# CM5_Adapter.net
KiCad netlist of a schematic drawn in Altium Designer
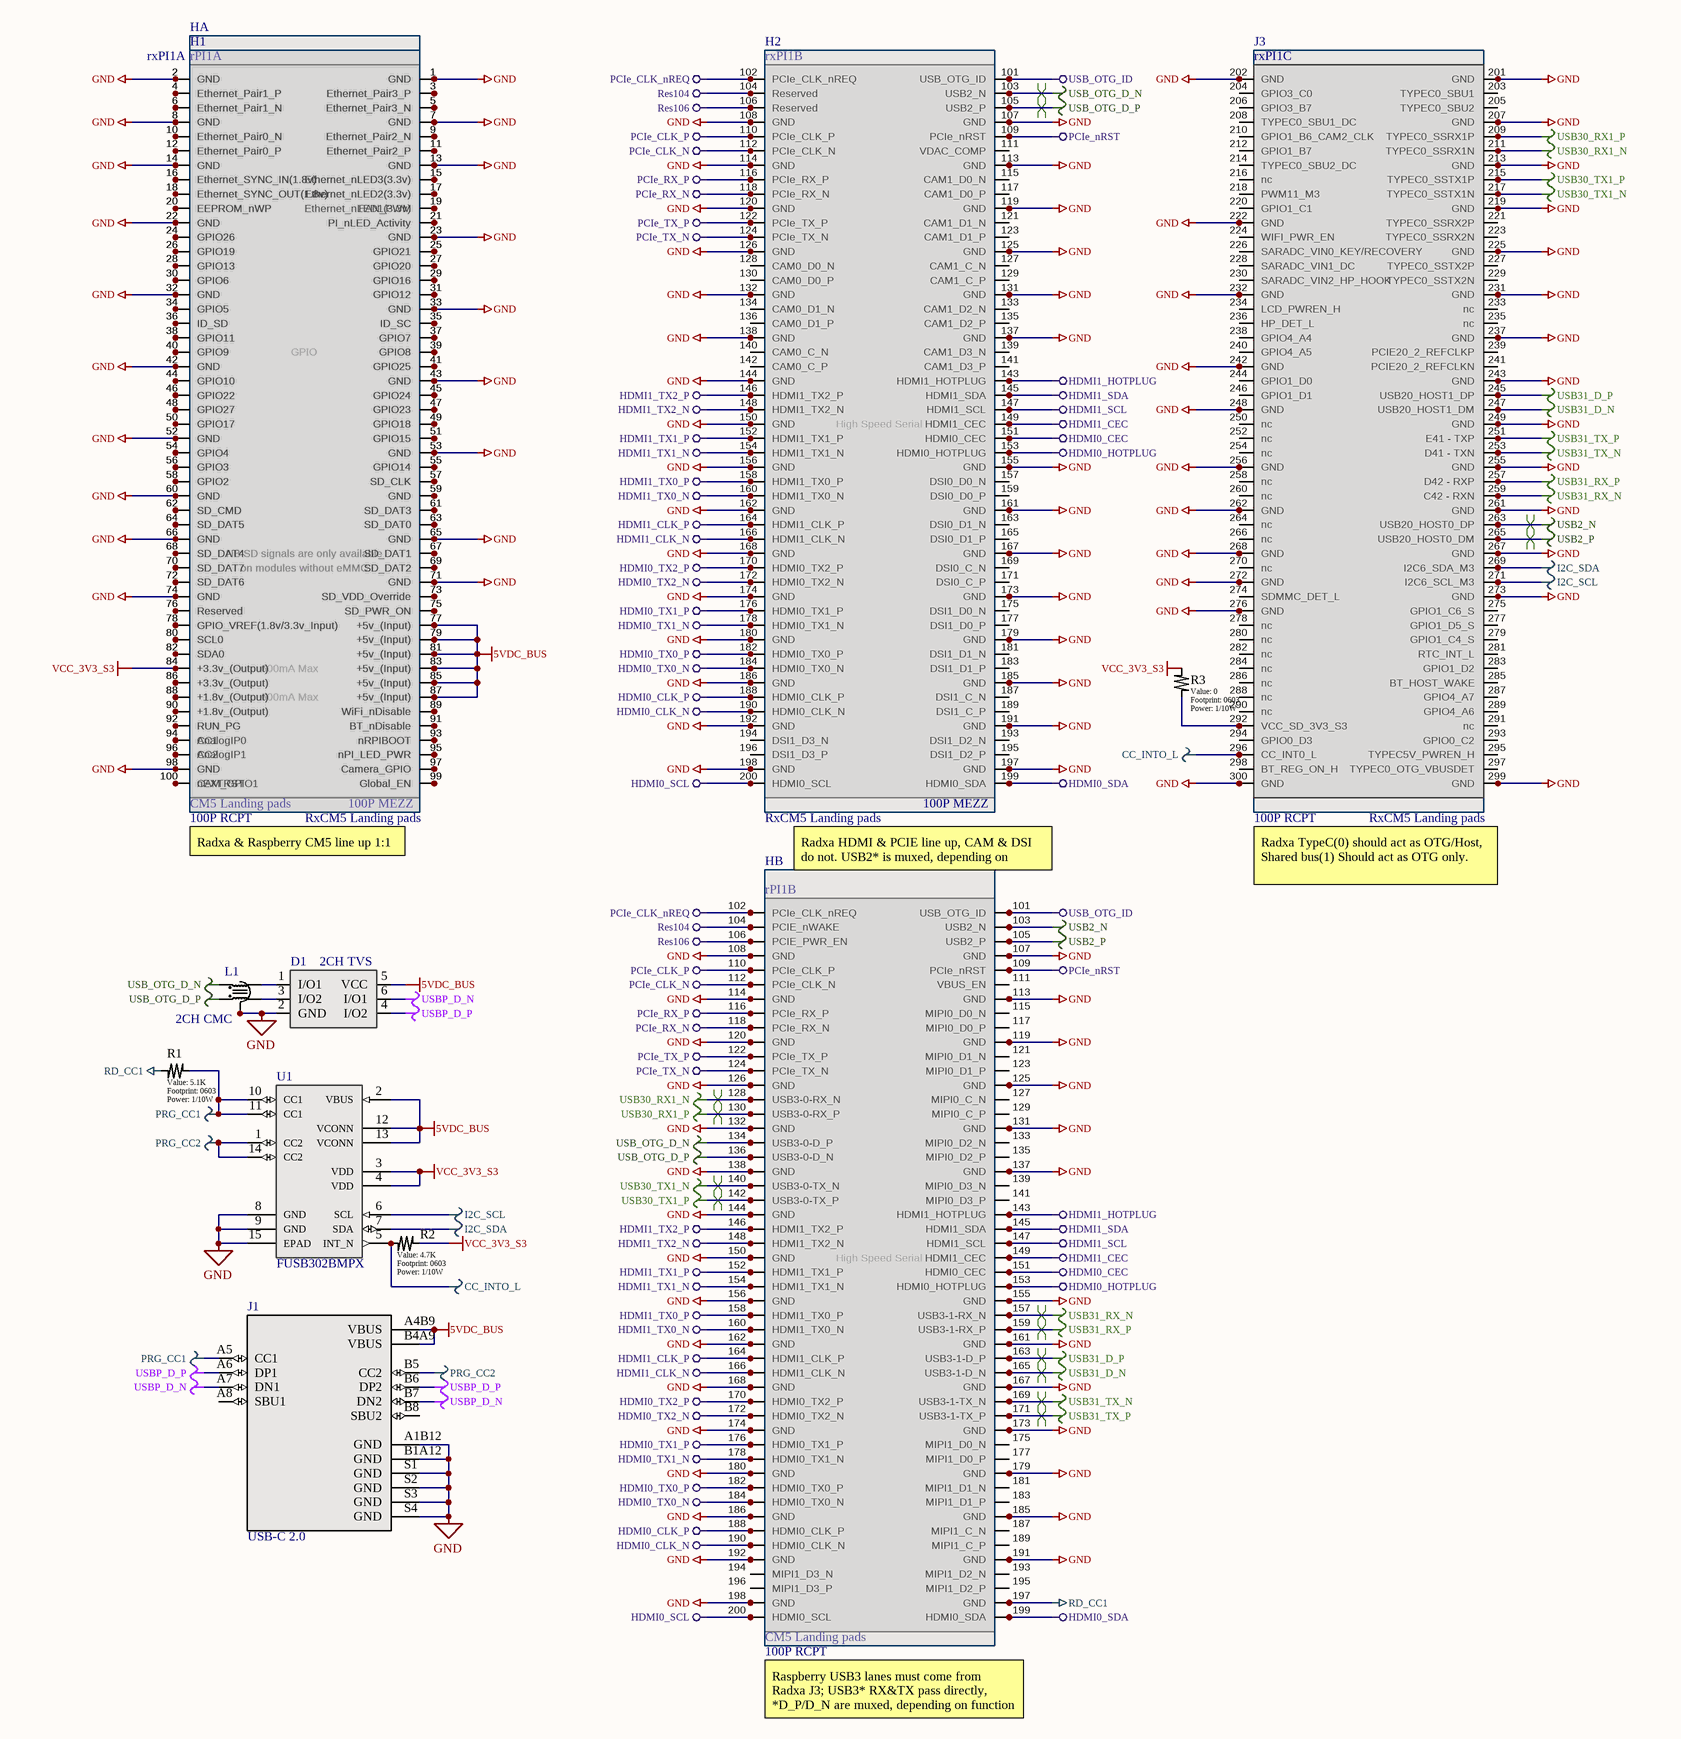
[diagram p0: CM5 Adapter.SchDoc]

(export (version "E")
  (design (tool "Eeschema 10.0.6"))
  (components
    (comp (ref "D1")
      (value "2CH TVS")
      (footprint "FP-SOT886-MFG")
      (description "TVS DIODE 5.5V 6XSON SOT886")
      (fields
        (field (name "OCTOPART") "https://octopart.com/prtr5v0u2f%2C115-nexperia-78741690")
        (field (name "MANUFACTURER") "Nexperia")
      )
      (libsource (lib "Diodes") (part "PRTR5V0U2F,115"))
    )
    (comp (ref "H1")
      (value "100P RCPT")
      (footprint "DF40C-100DS-0.4V(51)")
      (description "100 Position Connector Receptacle, Center Strip Contacts Surface Mount Gold")
      (fields (field (name "MF") "Hirose") (field (name "MP") "DF40C-100DS-0.4V(51)"))
      (libsource (lib "Connectors") (part "DF40-100DS RCPT_1"))
    )
    (comp (ref "H2")
      (value "100P MEZZ")
      (footprint "DF40C-100DS-0.4V(51)")
      (description "100 Position Connector Receptacle, Center Strip Contacts Surface Mount Gold")
      (fields (field (name "MF") "Hirose") (field (name "MP") "DF40C-100DS-0.4V(51)"))
      (libsource (lib "Connectors") (part "DF40-100DS RCPT_1"))
    )
    (comp (ref "HA")
      (value "100P MEZZ")
      (footprint "DF40C-100DP-0.4V(51)")
      (description "100 Position Connector Receptacle, Center Strip Contacts Surface Mount Gold")
      (fields (field (name "MF") "Hirose") (field (name "MP") "DF40C-100DS-0.4V(51)"))
      (libsource (lib "SOC_Carrier") (part "DF40-XX-100DS RCPT"))
    )
    (comp (ref "HB")
      (value "100P RCPT")
      (footprint "DF40C-100DP-0.4V(51)")
      (description "100 Position Connector Receptacle, Center Strip Contacts Surface Mount Gold")
      (fields (field (name "MF") "Hirose") (field (name "MP") "DF40C-100DS-0.4V(51)"))
      (libsource (lib "SOC_Carrier") (part "DF40-XX-100DS RCPT"))
    )
    (comp (ref "J1")
      (value "USB-C 2.0")
      (footprint "GT-USB-7010ASV")
      (libsource (lib "Connectors") (part "12402012E212A"))
    )
    (comp (ref "J3")
      (value "100P RCPT")
      (footprint "DF40C-100DS-0.4V(51)")
      (description "100 Position Connector Receptacle, Center Strip Contacts Surface Mount Gold")
      (fields (field (name "MF") "Hirose") (field (name "MP") "DF40C-100DS-0.4V(51)"))
      (libsource (lib "") (part "DF40-100DS RCPT_1_1"))
    )
    (comp (ref "L1")
      (value "2CH CMC")
      (footprint "SMD-6-2CH")
      (description "35Ω@100MHz -40℃~+85℃ 4Ω 5V 2 100mA SMD Common Mode Filters ROHS")
      (libsource (lib "Inductors") (part "ICMEF112P350MFR"))
    )
    (comp (ref "R1")
      (value "5.1K")
      (footprint "0603")
      (fields
        (field (name "TOLERANCE") "1%")
        (field (name "POWER") "1/10W")
        (field (name "Comment") "Generic Resistor")
      )
      (libsource (lib "Resistors") (part "Generic Resistor"))
    )
    (comp (ref "R2")
      (value "4.7K")
      (footprint "0603")
      (fields
        (field (name "TOLERANCE") "1%")
        (field (name "POWER") "1/10W")
        (field (name "Comment") "Generic Resistor")
      )
      (libsource (lib "Resistors") (part "Generic Resistor"))
    )
    (comp (ref "R3")
      (value "0")
      (footprint "0603")
      (fields
        (field (name "TOLERANCE") "1%")
        (field (name "POWER") "1/10W")
        (field (name "Comment") "Generic Resistor")
      )
      (libsource (lib "Resistors") (part "Generic Resistor"))
    )
    (comp (ref "rPI1")
      (value "CM5 Landing pads")
      (footprint "rP-200P-CM-REP (top)")
      (libsource (lib "SOC_Carrier") (part "RP-CM5-Rep"))
    )
    (comp (ref "rxPI1")
      (value "RxCM5 Landing pads")
      (footprint "RX-300P-CM-FTPD")
      (libsource (lib "SOC_Carrier") (part "RX-CM5"))
    )
    (comp (ref "U1")
      (value "FUSB302BMPX")
      (footprint "MLP14_2P5X2P5_ONS-L")
      (description "IC USB TYPE C CTLR PROGR 14-MLP")
      (fields (field (name "COPYRIGHT") "Copyright (C) 2025 Ultra Librarian. All rights reserved."))
      (libsource (lib "Misc ICs") (part "FUSB302BMPX"))
    )
  )
  (nets
    (net (code "1") (name "5VDC_BUS") (class "Default")
      (node (ref "D1") (pin "5") (pinfunction "VCC_5") (pintype "power_in"))
      (node (ref "H1") (pin "77") (pinfunction "77_77") (pintype "passive"))
      (node (ref "H1") (pin "79") (pinfunction "79_79") (pintype "passive"))
      (node (ref "H1") (pin "81") (pinfunction "81_81") (pintype "passive"))
      (node (ref "H1") (pin "83") (pinfunction "83_83") (pintype "passive"))
      (node (ref "H1") (pin "85") (pinfunction "85_85") (pintype "passive"))
      (node (ref "H1") (pin "87") (pinfunction "87_87") (pintype "passive"))
      (node (ref "HA") (pin "78") (pinfunction "78_78") (pintype "passive"))
      (node (ref "HA") (pin "80") (pinfunction "80_80") (pintype "passive"))
      (node (ref "HA") (pin "82") (pinfunction "82_82") (pintype "passive"))
      (node (ref "HA") (pin "84") (pinfunction "84_84") (pintype "passive"))
      (node (ref "HA") (pin "86") (pinfunction "86_86") (pintype "passive"))
      (node (ref "HA") (pin "88") (pinfunction "88_88") (pintype "passive"))
      (node (ref "J1") (pin "A4B9") (pinfunction "VBUS_A4B9") (pintype "power_in"))
      (node (ref "J1") (pin "B4A9") (pinfunction "VBUS_B4A9") (pintype "power_in"))
      (node (ref "U1") (pin "12") (pinfunction "VCONN_12") (pintype "power_in"))
      (node (ref "U1") (pin "13") (pinfunction "VCONN_13") (pintype "power_in"))
      (node (ref "U1") (pin "2") (pinfunction "VBUS_2") (pintype "input"))
      (node (ref "rPI1") (pin "77") (pinfunction "+5v_(Input)_77") (pintype "passive"))
      (node (ref "rPI1") (pin "79") (pinfunction "+5v_(Input)_79") (pintype "passive"))
      (node (ref "rPI1") (pin "81") (pinfunction "+5v_(Input)_81") (pintype "passive"))
      (node (ref "rPI1") (pin "83") (pinfunction "+5v_(Input)_83") (pintype "passive"))
      (node (ref "rPI1") (pin "85") (pinfunction "+5v_(Input)_85") (pintype "passive"))
      (node (ref "rPI1") (pin "87") (pinfunction "+5v_(Input)_87") (pintype "passive"))
      (node (ref "rxPI1") (pin "77") (pinfunction "+5v_(Input)_77") (pintype "passive"))
      (node (ref "rxPI1") (pin "79") (pinfunction "+5v_(Input)_79") (pintype "passive"))
      (node (ref "rxPI1") (pin "81") (pinfunction "+5v_(Input)_81") (pintype "passive"))
      (node (ref "rxPI1") (pin "83") (pinfunction "+5v_(Input)_83") (pintype "passive"))
      (node (ref "rxPI1") (pin "85") (pinfunction "+5v_(Input)_85") (pintype "passive"))
      (node (ref "rxPI1") (pin "87") (pinfunction "+5v_(Input)_87") (pintype "passive"))
    )
    (net (code "2") (name "CC_INTO_L") (class "Default")
      (node (ref "J3") (pin "95") (pinfunction "95_95") (pintype "passive"))
      (node (ref "R2") (pin "1") (pinfunction "1_1") (pintype "passive"))
      (node (ref "U1") (pin "5") (pinfunction "INT_N_5") (pintype "output"))
      (node (ref "rxPI1") (pin "296") (pinfunction "CC_INT0_L_296") (pintype "passive"))
    )
    (net (code "3") (name "GND") (class "Default")
      (node (ref "D1") (pin "2") (pinfunction "GND_2") (pintype "power_in"))
      (node (ref "H1") (pin "1") (pinfunction "1_1") (pintype "passive"))
      (node (ref "H1") (pin "13") (pinfunction "13_13") (pintype "passive"))
      (node (ref "H1") (pin "14") (pinfunction "14_14") (pintype "passive"))
      (node (ref "H1") (pin "2") (pinfunction "2_2") (pintype "passive"))
      (node (ref "H1") (pin "22") (pinfunction "22_22") (pintype "passive"))
      (node (ref "H1") (pin "23") (pinfunction "23_23") (pintype "passive"))
      (node (ref "H1") (pin "32") (pinfunction "32_32") (pintype "passive"))
      (node (ref "H1") (pin "33") (pinfunction "33_33") (pintype "passive"))
      (node (ref "H1") (pin "42") (pinfunction "42_42") (pintype "passive"))
      (node (ref "H1") (pin "43") (pinfunction "43_43") (pintype "passive"))
      (node (ref "H1") (pin "52") (pinfunction "52_52") (pintype "passive"))
      (node (ref "H1") (pin "53") (pinfunction "53_53") (pintype "passive"))
      (node (ref "H1") (pin "60") (pinfunction "60_60") (pintype "passive"))
      (node (ref "H1") (pin "65") (pinfunction "65_65") (pintype "passive"))
      (node (ref "H1") (pin "66") (pinfunction "66_66") (pintype "passive"))
      (node (ref "H1") (pin "7") (pinfunction "7_7") (pintype "passive"))
      (node (ref "H1") (pin "71") (pinfunction "71_71") (pintype "passive"))
      (node (ref "H1") (pin "74") (pinfunction "74_74") (pintype "passive"))
      (node (ref "H1") (pin "8") (pinfunction "8_8") (pintype "passive"))
      (node (ref "H1") (pin "98") (pinfunction "98_98") (pintype "passive"))
      (node (ref "H2") (pin "13") (pinfunction "13_13") (pintype "passive"))
      (node (ref "H2") (pin "14") (pinfunction "14_14") (pintype "passive"))
      (node (ref "H2") (pin "19") (pinfunction "19_19") (pintype "passive"))
      (node (ref "H2") (pin "20") (pinfunction "20_20") (pintype "passive"))
      (node (ref "H2") (pin "25") (pinfunction "25_25") (pintype "passive"))
      (node (ref "H2") (pin "26") (pinfunction "26_26") (pintype "passive"))
      (node (ref "H2") (pin "31") (pinfunction "31_31") (pintype "passive"))
      (node (ref "H2") (pin "32") (pinfunction "32_32") (pintype "passive"))
      (node (ref "H2") (pin "37") (pinfunction "37_37") (pintype "passive"))
      (node (ref "H2") (pin "38") (pinfunction "38_38") (pintype "passive"))
      (node (ref "H2") (pin "44") (pinfunction "44_44") (pintype "passive"))
      (node (ref "H2") (pin "50") (pinfunction "50_50") (pintype "passive"))
      (node (ref "H2") (pin "55") (pinfunction "55_55") (pintype "passive"))
      (node (ref "H2") (pin "56") (pinfunction "56_56") (pintype "passive"))
      (node (ref "H2") (pin "61") (pinfunction "61_61") (pintype "passive"))
      (node (ref "H2") (pin "62") (pinfunction "62_62") (pintype "passive"))
      (node (ref "H2") (pin "67") (pinfunction "67_67") (pintype "passive"))
      (node (ref "H2") (pin "68") (pinfunction "68_68") (pintype "passive"))
      (node (ref "H2") (pin "7") (pinfunction "7_7") (pintype "passive"))
      (node (ref "H2") (pin "73") (pinfunction "73_73") (pintype "passive"))
      (node (ref "H2") (pin "74") (pinfunction "74_74") (pintype "passive"))
      (node (ref "H2") (pin "79") (pinfunction "79_79") (pintype "passive"))
      (node (ref "H2") (pin "8") (pinfunction "8_8") (pintype "passive"))
      (node (ref "H2") (pin "80") (pinfunction "80_80") (pintype "passive"))
      (node (ref "H2") (pin "85") (pinfunction "85_85") (pintype "passive"))
      (node (ref "H2") (pin "86") (pinfunction "86_86") (pintype "passive"))
      (node (ref "H2") (pin "91") (pinfunction "91_91") (pintype "passive"))
      (node (ref "H2") (pin "92") (pinfunction "92_92") (pintype "passive"))
      (node (ref "H2") (pin "97") (pinfunction "97_97") (pintype "passive"))
      (node (ref "H2") (pin "98") (pinfunction "98_98") (pintype "passive"))
      (node (ref "HA") (pin "1") (pinfunction "1_1") (pintype "passive"))
      (node (ref "HA") (pin "13") (pinfunction "13_13") (pintype "passive"))
      (node (ref "HA") (pin "14") (pinfunction "14_14") (pintype "passive"))
      (node (ref "HA") (pin "2") (pinfunction "2_2") (pintype "passive"))
      (node (ref "HA") (pin "21") (pinfunction "21_21") (pintype "passive"))
      (node (ref "HA") (pin "24") (pinfunction "24_24") (pintype "passive"))
      (node (ref "HA") (pin "31") (pinfunction "31_31") (pintype "passive"))
      (node (ref "HA") (pin "34") (pinfunction "34_34") (pintype "passive"))
      (node (ref "HA") (pin "41") (pinfunction "41_41") (pintype "passive"))
      (node (ref "HA") (pin "44") (pinfunction "44_44") (pintype "passive"))
      (node (ref "HA") (pin "51") (pinfunction "51_51") (pintype "passive"))
      (node (ref "HA") (pin "54") (pinfunction "54_54") (pintype "passive"))
      (node (ref "HA") (pin "59") (pinfunction "59_59") (pintype "passive"))
      (node (ref "HA") (pin "65") (pinfunction "65_65") (pintype "passive"))
      (node (ref "HA") (pin "66") (pinfunction "66_66") (pintype "passive"))
      (node (ref "HA") (pin "7") (pinfunction "7_7") (pintype "passive"))
      (node (ref "HA") (pin "72") (pinfunction "72_72") (pintype "passive"))
      (node (ref "HA") (pin "73") (pinfunction "73_73") (pintype "passive"))
      (node (ref "HA") (pin "8") (pinfunction "8_8") (pintype "passive"))
      (node (ref "HA") (pin "97") (pinfunction "97_97") (pintype "passive"))
      (node (ref "HB") (pin "13") (pinfunction "13_13") (pintype "passive"))
      (node (ref "HB") (pin "14") (pinfunction "14_14") (pintype "passive"))
      (node (ref "HB") (pin "19") (pinfunction "19_19") (pintype "passive"))
      (node (ref "HB") (pin "20") (pinfunction "20_20") (pintype "passive"))
      (node (ref "HB") (pin "25") (pinfunction "25_25") (pintype "passive"))
      (node (ref "HB") (pin "26") (pinfunction "26_26") (pintype "passive"))
      (node (ref "HB") (pin "31") (pinfunction "31_31") (pintype "passive"))
      (node (ref "HB") (pin "32") (pinfunction "32_32") (pintype "passive"))
      (node (ref "HB") (pin "37") (pinfunction "37_37") (pintype "passive"))
      (node (ref "HB") (pin "38") (pinfunction "38_38") (pintype "passive"))
      (node (ref "HB") (pin "43") (pinfunction "43_43") (pintype "passive"))
      (node (ref "HB") (pin "49") (pinfunction "49_49") (pintype "passive"))
      (node (ref "HB") (pin "55") (pinfunction "55_55") (pintype "passive"))
      (node (ref "HB") (pin "56") (pinfunction "56_56") (pintype "passive"))
      (node (ref "HB") (pin "61") (pinfunction "61_61") (pintype "passive"))
      (node (ref "HB") (pin "62") (pinfunction "62_62") (pintype "passive"))
      (node (ref "HB") (pin "67") (pinfunction "67_67") (pintype "passive"))
      (node (ref "HB") (pin "68") (pinfunction "68_68") (pintype "passive"))
      (node (ref "HB") (pin "7") (pinfunction "7_7") (pintype "passive"))
      (node (ref "HB") (pin "73") (pinfunction "73_73") (pintype "passive"))
      (node (ref "HB") (pin "74") (pinfunction "74_74") (pintype "passive"))
      (node (ref "HB") (pin "79") (pinfunction "79_79") (pintype "passive"))
      (node (ref "HB") (pin "8") (pinfunction "8_8") (pintype "passive"))
      (node (ref "HB") (pin "80") (pinfunction "80_80") (pintype "passive"))
      (node (ref "HB") (pin "85") (pinfunction "85_85") (pintype "passive"))
      (node (ref "HB") (pin "86") (pinfunction "86_86") (pintype "passive"))
      (node (ref "HB") (pin "91") (pinfunction "91_91") (pintype "passive"))
      (node (ref "HB") (pin "92") (pinfunction "92_92") (pintype "passive"))
      (node (ref "HB") (pin "97") (pinfunction "97_97") (pintype "passive"))
      (node (ref "J1") (pin "A1B12") (pinfunction "GND_A1B12") (pintype "power_in"))
      (node (ref "J1") (pin "B1A12") (pinfunction "GND_B1A12") (pintype "power_in"))
      (node (ref "J1") (pin "S1") (pinfunction "GND_S1") (pintype "power_in"))
      (node (ref "J1") (pin "S2") (pinfunction "GND_S2") (pintype "power_in"))
      (node (ref "J1") (pin "S3") (pinfunction "GND_S3") (pintype "power_in"))
      (node (ref "J1") (pin "S4") (pinfunction "GND_S4") (pintype "power_in"))
      (node (ref "J3") (pin "1") (pinfunction "1_1") (pintype "passive"))
      (node (ref "J3") (pin "100") (pinfunction "100_100") (pintype "passive"))
      (node (ref "J3") (pin "14") (pinfunction "14_14") (pintype "passive"))
      (node (ref "J3") (pin "2") (pinfunction "2_2") (pintype "passive"))
      (node (ref "J3") (pin "20") (pinfunction "20_20") (pintype "passive"))
      (node (ref "J3") (pin "21") (pinfunction "21_21") (pintype "passive"))
      (node (ref "J3") (pin "26") (pinfunction "26_26") (pintype "passive"))
      (node (ref "J3") (pin "31") (pinfunction "31_31") (pintype "passive"))
      (node (ref "J3") (pin "32") (pinfunction "32_32") (pintype "passive"))
      (node (ref "J3") (pin "38") (pinfunction "38_38") (pintype "passive"))
      (node (ref "J3") (pin "41") (pinfunction "41_41") (pintype "passive"))
      (node (ref "J3") (pin "44") (pinfunction "44_44") (pintype "passive"))
      (node (ref "J3") (pin "47") (pinfunction "47_47") (pintype "passive"))
      (node (ref "J3") (pin "50") (pinfunction "50_50") (pintype "passive"))
      (node (ref "J3") (pin "55") (pinfunction "55_55") (pintype "passive"))
      (node (ref "J3") (pin "56") (pinfunction "56_56") (pintype "passive"))
      (node (ref "J3") (pin "61") (pinfunction "61_61") (pintype "passive"))
      (node (ref "J3") (pin "62") (pinfunction "62_62") (pintype "passive"))
      (node (ref "J3") (pin "67") (pinfunction "67_67") (pintype "passive"))
      (node (ref "J3") (pin "68") (pinfunction "68_68") (pintype "passive"))
      (node (ref "J3") (pin "71") (pinfunction "71_71") (pintype "passive"))
      (node (ref "J3") (pin "74") (pinfunction "74_74") (pintype "passive"))
      (node (ref "J3") (pin "75") (pinfunction "75_75") (pintype "passive"))
      (node (ref "J3") (pin "8") (pinfunction "8_8") (pintype "passive"))
      (node (ref "J3") (pin "99") (pinfunction "99_99") (pintype "passive"))
      (node (ref "L1") (pin "5") (pinfunction "5_5") (pintype "passive"))
      (node (ref "L1") (pin "6") (pinfunction "6_6") (pintype "passive"))
      (node (ref "U1") (pin "15") (pinfunction "EPAD_15") (pintype "passive"))
      (node (ref "U1") (pin "8") (pinfunction "GND_8") (pintype "power_in"))
      (node (ref "U1") (pin "9") (pinfunction "GND_9") (pintype "power_in"))
      (node (ref "rPI1") (pin "1") (pinfunction "GND_1") (pintype "passive"))
      (node (ref "rPI1") (pin "107") (pinfunction "GND_107") (pintype "passive"))
      (node (ref "rPI1") (pin "108") (pinfunction "GND_108") (pintype "passive"))
      (node (ref "rPI1") (pin "113") (pinfunction "GND_113") (pintype "passive"))
      (node (ref "rPI1") (pin "114") (pinfunction "GND_114") (pintype "passive"))
      (node (ref "rPI1") (pin "119") (pinfunction "GND_119") (pintype "passive"))
      (node (ref "rPI1") (pin "120") (pinfunction "GND_120") (pintype "passive"))
      (node (ref "rPI1") (pin "125") (pinfunction "GND_125") (pintype "passive"))
      (node (ref "rPI1") (pin "126") (pinfunction "GND_126") (pintype "passive"))
      (node (ref "rPI1") (pin "13") (pinfunction "GND_13") (pintype "passive"))
      (node (ref "rPI1") (pin "131") (pinfunction "GND_131") (pintype "passive"))
      (node (ref "rPI1") (pin "132") (pinfunction "GND_132") (pintype "passive"))
      (node (ref "rPI1") (pin "137") (pinfunction "GND_137") (pintype "passive"))
      (node (ref "rPI1") (pin "138") (pinfunction "GND_138") (pintype "passive"))
      (node (ref "rPI1") (pin "14") (pinfunction "GND_14") (pintype "passive"))
      (node (ref "rPI1") (pin "144") (pinfunction "GND_144") (pintype "passive"))
      (node (ref "rPI1") (pin "150") (pinfunction "GND_150") (pintype "passive"))
      (node (ref "rPI1") (pin "155") (pinfunction "GND_155") (pintype "passive"))
      (node (ref "rPI1") (pin "156") (pinfunction "GND_156") (pintype "passive"))
      (node (ref "rPI1") (pin "161") (pinfunction "GND_161") (pintype "passive"))
      (node (ref "rPI1") (pin "162") (pinfunction "GND_162") (pintype "passive"))
      (node (ref "rPI1") (pin "167") (pinfunction "GND_167") (pintype "passive"))
      (node (ref "rPI1") (pin "168") (pinfunction "GND_168") (pintype "passive"))
      (node (ref "rPI1") (pin "173") (pinfunction "GND_173") (pintype "passive"))
      (node (ref "rPI1") (pin "174") (pinfunction "GND_174") (pintype "passive"))
      (node (ref "rPI1") (pin "179") (pinfunction "GND_179") (pintype "passive"))
      (node (ref "rPI1") (pin "180") (pinfunction "GND_180") (pintype "passive"))
      (node (ref "rPI1") (pin "185") (pinfunction "GND_185") (pintype "passive"))
      (node (ref "rPI1") (pin "186") (pinfunction "GND_186") (pintype "passive"))
      (node (ref "rPI1") (pin "191") (pinfunction "GND_191") (pintype "passive"))
      (node (ref "rPI1") (pin "192") (pinfunction "GND_192") (pintype "passive"))
      (node (ref "rPI1") (pin "198") (pinfunction "GND_198") (pintype "passive"))
      (node (ref "rPI1") (pin "2") (pinfunction "GND_2") (pintype "passive"))
      (node (ref "rPI1") (pin "22") (pinfunction "GND_22") (pintype "passive"))
      (node (ref "rPI1") (pin "23") (pinfunction "GND_23") (pintype "passive"))
      (node (ref "rPI1") (pin "32") (pinfunction "GND_32") (pintype "passive"))
      (node (ref "rPI1") (pin "33") (pinfunction "GND_33") (pintype "passive"))
      (node (ref "rPI1") (pin "42") (pinfunction "GND_42") (pintype "passive"))
      (node (ref "rPI1") (pin "43") (pinfunction "GND_43") (pintype "passive"))
      (node (ref "rPI1") (pin "52") (pinfunction "GND_52") (pintype "passive"))
      (node (ref "rPI1") (pin "53") (pinfunction "GND_53") (pintype "passive"))
      (node (ref "rPI1") (pin "60") (pinfunction "GND_60") (pintype "passive"))
      (node (ref "rPI1") (pin "65") (pinfunction "GND_65") (pintype "passive"))
      (node (ref "rPI1") (pin "66") (pinfunction "GND_66") (pintype "passive"))
      (node (ref "rPI1") (pin "7") (pinfunction "GND_7") (pintype "passive"))
      (node (ref "rPI1") (pin "71") (pinfunction "GND_71") (pintype "passive"))
      (node (ref "rPI1") (pin "74") (pinfunction "GND_74") (pintype "passive"))
      (node (ref "rPI1") (pin "8") (pinfunction "GND_8") (pintype "passive"))
      (node (ref "rPI1") (pin "98") (pinfunction "GND_98") (pintype "passive"))
      (node (ref "rxPI1") (pin "1") (pinfunction "GND_1") (pintype "passive"))
      (node (ref "rxPI1") (pin "107") (pinfunction "GND_107") (pintype "passive"))
      (node (ref "rxPI1") (pin "108") (pinfunction "GND_108") (pintype "passive"))
      (node (ref "rxPI1") (pin "113") (pinfunction "GND_113") (pintype "passive"))
      (node (ref "rxPI1") (pin "114") (pinfunction "GND_114") (pintype "passive"))
      (node (ref "rxPI1") (pin "119") (pinfunction "GND_119") (pintype "passive"))
      (node (ref "rxPI1") (pin "120") (pinfunction "GND_120") (pintype "passive"))
      (node (ref "rxPI1") (pin "125") (pinfunction "GND_125") (pintype "passive"))
      (node (ref "rxPI1") (pin "126") (pinfunction "GND_126") (pintype "passive"))
      (node (ref "rxPI1") (pin "13") (pinfunction "GND_13") (pintype "passive"))
      (node (ref "rxPI1") (pin "131") (pinfunction "GND_131") (pintype "passive"))
      (node (ref "rxPI1") (pin "132") (pinfunction "GND_132") (pintype "passive"))
      (node (ref "rxPI1") (pin "137") (pinfunction "GND_137") (pintype "passive"))
      (node (ref "rxPI1") (pin "138") (pinfunction "GND_138") (pintype "passive"))
      (node (ref "rxPI1") (pin "14") (pinfunction "GND_14") (pintype "passive"))
      (node (ref "rxPI1") (pin "144") (pinfunction "GND_144") (pintype "passive"))
      (node (ref "rxPI1") (pin "150") (pinfunction "GND_150") (pintype "passive"))
      (node (ref "rxPI1") (pin "155") (pinfunction "GND_155") (pintype "passive"))
      (node (ref "rxPI1") (pin "156") (pinfunction "GND_156") (pintype "passive"))
      (node (ref "rxPI1") (pin "161") (pinfunction "GND_161") (pintype "passive"))
      (node (ref "rxPI1") (pin "162") (pinfunction "GND_162") (pintype "passive"))
      (node (ref "rxPI1") (pin "167") (pinfunction "GND_167") (pintype "passive"))
      (node (ref "rxPI1") (pin "168") (pinfunction "GND_168") (pintype "passive"))
      (node (ref "rxPI1") (pin "173") (pinfunction "GND_173") (pintype "passive"))
      (node (ref "rxPI1") (pin "174") (pinfunction "GND_174") (pintype "passive"))
      (node (ref "rxPI1") (pin "179") (pinfunction "GND_179") (pintype "passive"))
      (node (ref "rxPI1") (pin "180") (pinfunction "GND_180") (pintype "passive"))
      (node (ref "rxPI1") (pin "185") (pinfunction "GND_185") (pintype "passive"))
      (node (ref "rxPI1") (pin "186") (pinfunction "GND_186") (pintype "passive"))
      (node (ref "rxPI1") (pin "191") (pinfunction "GND_191") (pintype "passive"))
      (node (ref "rxPI1") (pin "192") (pinfunction "GND_192") (pintype "passive"))
      (node (ref "rxPI1") (pin "197") (pinfunction "GND_197") (pintype "passive"))
      (node (ref "rxPI1") (pin "198") (pinfunction "GND_198") (pintype "passive"))
      (node (ref "rxPI1") (pin "2") (pinfunction "GND_2") (pintype "passive"))
      (node (ref "rxPI1") (pin "201") (pinfunction "GND_201") (pintype "passive"))
      (node (ref "rxPI1") (pin "202") (pinfunction "GND_202") (pintype "passive"))
      (node (ref "rxPI1") (pin "207") (pinfunction "GND_207") (pintype "passive"))
      (node (ref "rxPI1") (pin "213") (pinfunction "GND_213") (pintype "passive"))
      (node (ref "rxPI1") (pin "219") (pinfunction "GND_219") (pintype "passive"))
      (node (ref "rxPI1") (pin "22") (pinfunction "GND_22") (pintype "passive"))
      (node (ref "rxPI1") (pin "222") (pinfunction "GND_222") (pintype "passive"))
      (node (ref "rxPI1") (pin "225") (pinfunction "GND_225") (pintype "passive"))
      (node (ref "rxPI1") (pin "23") (pinfunction "GND_23") (pintype "passive"))
      (node (ref "rxPI1") (pin "231") (pinfunction "GND_231") (pintype "passive"))
      (node (ref "rxPI1") (pin "232") (pinfunction "GND_232") (pintype "passive"))
      (node (ref "rxPI1") (pin "237") (pinfunction "GND_237") (pintype "passive"))
      (node (ref "rxPI1") (pin "242") (pinfunction "GND_242") (pintype "passive"))
      (node (ref "rxPI1") (pin "243") (pinfunction "GND_243") (pintype "passive"))
      (node (ref "rxPI1") (pin "248") (pinfunction "GND_248") (pintype "passive"))
      (node (ref "rxPI1") (pin "249") (pinfunction "GND_249") (pintype "passive"))
      (node (ref "rxPI1") (pin "255") (pinfunction "GND_255") (pintype "passive"))
      (node (ref "rxPI1") (pin "256") (pinfunction "GND_256") (pintype "passive"))
      (node (ref "rxPI1") (pin "261") (pinfunction "GND_261") (pintype "passive"))
      (node (ref "rxPI1") (pin "262") (pinfunction "GND_262") (pintype "passive"))
      (node (ref "rxPI1") (pin "267") (pinfunction "GND_267") (pintype "passive"))
      (node (ref "rxPI1") (pin "268") (pinfunction "GND_268") (pintype "passive"))
      (node (ref "rxPI1") (pin "272") (pinfunction "GND_272") (pintype "passive"))
      (node (ref "rxPI1") (pin "273") (pinfunction "GND_273") (pintype "passive"))
      (node (ref "rxPI1") (pin "276") (pinfunction "GND_276") (pintype "passive"))
      (node (ref "rxPI1") (pin "299") (pinfunction "GND_299") (pintype "passive"))
      (node (ref "rxPI1") (pin "300") (pinfunction "GND_300") (pintype "passive"))
      (node (ref "rxPI1") (pin "32") (pinfunction "GND_32") (pintype "passive"))
      (node (ref "rxPI1") (pin "33") (pinfunction "GND_33") (pintype "passive"))
      (node (ref "rxPI1") (pin "42") (pinfunction "GND_42") (pintype "passive"))
      (node (ref "rxPI1") (pin "43") (pinfunction "GND_43") (pintype "passive"))
      (node (ref "rxPI1") (pin "52") (pinfunction "GND_52") (pintype "passive"))
      (node (ref "rxPI1") (pin "53") (pinfunction "GND_53") (pintype "passive"))
      (node (ref "rxPI1") (pin "60") (pinfunction "GND_60") (pintype "passive"))
      (node (ref "rxPI1") (pin "65") (pinfunction "GND_65") (pintype "passive"))
      (node (ref "rxPI1") (pin "66") (pinfunction "GND_66") (pintype "passive"))
      (node (ref "rxPI1") (pin "7") (pinfunction "GND_7") (pintype "passive"))
      (node (ref "rxPI1") (pin "71") (pinfunction "GND_71") (pintype "passive"))
      (node (ref "rxPI1") (pin "74") (pinfunction "GND_74") (pintype "passive"))
      (node (ref "rxPI1") (pin "8") (pinfunction "GND_8") (pintype "passive"))
      (node (ref "rxPI1") (pin "98") (pinfunction "GND_98") (pintype "passive"))
    )
    (net (code "4") (name "HDMI0_CEC") (class "Default")
      (node (ref "H2") (pin "51") (pinfunction "51_51") (pintype "passive"))
      (node (ref "HB") (pin "52") (pinfunction "52_52") (pintype "passive"))
      (node (ref "rPI1") (pin "151") (pinfunction "HDMI0_CEC_151") (pintype "passive"))
      (node (ref "rxPI1") (pin "151") (pinfunction "HDMI0_CEC_151") (pintype "passive"))
    )
    (net (code "5") (name "HDMI0_CLK_N") (class "Default")
      (node (ref "H2") (pin "90") (pinfunction "90_90") (pintype "passive"))
      (node (ref "HB") (pin "89") (pinfunction "89_89") (pintype "passive"))
      (node (ref "rPI1") (pin "190") (pinfunction "HDMI0_CLK_N_190") (pintype "passive"))
      (node (ref "rxPI1") (pin "190") (pinfunction "HDMI0_CLK_N_190") (pintype "passive"))
    )
    (net (code "6") (name "HDMI0_CLK_P") (class "Default")
      (node (ref "H2") (pin "88") (pinfunction "88_88") (pintype "passive"))
      (node (ref "HB") (pin "87") (pinfunction "87_87") (pintype "passive"))
      (node (ref "rPI1") (pin "188") (pinfunction "HDMI0_CLK_P_188") (pintype "passive"))
      (node (ref "rxPI1") (pin "188") (pinfunction "HDMI0_CLK_P_188") (pintype "passive"))
    )
    (net (code "7") (name "HDMI0_HOTPLUG") (class "Default")
      (node (ref "H2") (pin "53") (pinfunction "53_53") (pintype "passive"))
      (node (ref "HB") (pin "54") (pinfunction "54_54") (pintype "passive"))
      (node (ref "rPI1") (pin "153") (pinfunction "HDMI0_HOTPLUG_153") (pintype "passive"))
      (node (ref "rxPI1") (pin "153") (pinfunction "HDMI0_HOTPLUG_153") (pintype "passive"))
    )
    (net (code "8") (name "HDMI0_SCL") (class "Default")
      (node (ref "H2") (pin "100") (pinfunction "100_100") (pintype "passive"))
      (node (ref "HB") (pin "99") (pinfunction "99_99") (pintype "passive"))
      (node (ref "rPI1") (pin "200") (pinfunction "HDMI0_SCL_200") (pintype "passive"))
      (node (ref "rxPI1") (pin "200") (pinfunction "HDMI0_SCL_200") (pintype "passive"))
    )
    (net (code "9") (name "HDMI0_SDA") (class "Default")
      (node (ref "H2") (pin "99") (pinfunction "99_99") (pintype "passive"))
      (node (ref "HB") (pin "100") (pinfunction "100_100") (pintype "passive"))
      (node (ref "rPI1") (pin "199") (pinfunction "HDMI0_SDA_199") (pintype "passive"))
      (node (ref "rxPI1") (pin "199") (pinfunction "HDMI0_SDA_199") (pintype "passive"))
    )
    (net (code "10") (name "HDMI0_TX0_N") (class "Default")
      (node (ref "H2") (pin "84") (pinfunction "84_84") (pintype "passive"))
      (node (ref "HB") (pin "83") (pinfunction "83_83") (pintype "passive"))
      (node (ref "rPI1") (pin "184") (pinfunction "HDMI0_TX0_N_184") (pintype "passive"))
      (node (ref "rxPI1") (pin "184") (pinfunction "HDMI0_TX0_N_184") (pintype "passive"))
    )
    (net (code "11") (name "HDMI0_TX0_P") (class "Default")
      (node (ref "H2") (pin "82") (pinfunction "82_82") (pintype "passive"))
      (node (ref "HB") (pin "81") (pinfunction "81_81") (pintype "passive"))
      (node (ref "rPI1") (pin "182") (pinfunction "HDMI0_TX0_P_182") (pintype "passive"))
      (node (ref "rxPI1") (pin "182") (pinfunction "HDMI0_TX0_P_182") (pintype "passive"))
    )
    (net (code "12") (name "HDMI0_TX1_N") (class "Default")
      (node (ref "H2") (pin "78") (pinfunction "78_78") (pintype "passive"))
      (node (ref "HB") (pin "77") (pinfunction "77_77") (pintype "passive"))
      (node (ref "rPI1") (pin "178") (pinfunction "HDMI0_TX1_N_178") (pintype "passive"))
      (node (ref "rxPI1") (pin "178") (pinfunction "HDMI0_TX1_N_178") (pintype "passive"))
    )
    (net (code "13") (name "HDMI0_TX1_P") (class "Default")
      (node (ref "H2") (pin "76") (pinfunction "76_76") (pintype "passive"))
      (node (ref "HB") (pin "75") (pinfunction "75_75") (pintype "passive"))
      (node (ref "rPI1") (pin "176") (pinfunction "HDMI0_TX1_P_176") (pintype "passive"))
      (node (ref "rxPI1") (pin "176") (pinfunction "HDMI0_TX1_P_176") (pintype "passive"))
    )
    (net (code "14") (name "HDMI0_TX2_N") (class "Default")
      (node (ref "H2") (pin "72") (pinfunction "72_72") (pintype "passive"))
      (node (ref "HB") (pin "71") (pinfunction "71_71") (pintype "passive"))
      (node (ref "rPI1") (pin "172") (pinfunction "HDMI0_TX2_N_172") (pintype "passive"))
      (node (ref "rxPI1") (pin "172") (pinfunction "HDMI0_TX2_N_172") (pintype "passive"))
    )
    (net (code "15") (name "HDMI0_TX2_P") (class "Default")
      (node (ref "H2") (pin "70") (pinfunction "70_70") (pintype "passive"))
      (node (ref "HB") (pin "69") (pinfunction "69_69") (pintype "passive"))
      (node (ref "rPI1") (pin "170") (pinfunction "HDMI0_TX2_P_170") (pintype "passive"))
      (node (ref "rxPI1") (pin "170") (pinfunction "HDMI0_TX2_P_170") (pintype "passive"))
    )
    (net (code "16") (name "HDMI1_CEC") (class "Default")
      (node (ref "H2") (pin "49") (pinfunction "49_49") (pintype "passive"))
      (node (ref "HB") (pin "50") (pinfunction "50_50") (pintype "passive"))
      (node (ref "rPI1") (pin "149") (pinfunction "HDMI1_CEC_149") (pintype "passive"))
      (node (ref "rxPI1") (pin "149") (pinfunction "HDMI1_CEC_149") (pintype "passive"))
    )
    (net (code "17") (name "HDMI1_CLK_N") (class "Default")
      (node (ref "H2") (pin "66") (pinfunction "66_66") (pintype "passive"))
      (node (ref "HB") (pin "65") (pinfunction "65_65") (pintype "passive"))
      (node (ref "rPI1") (pin "166") (pinfunction "HDMI1_CLK_N_166") (pintype "passive"))
      (node (ref "rxPI1") (pin "166") (pinfunction "HDMI1_CLK_N_166") (pintype "passive"))
    )
    (net (code "18") (name "HDMI1_CLK_P") (class "Default")
      (node (ref "H2") (pin "64") (pinfunction "64_64") (pintype "passive"))
      (node (ref "HB") (pin "63") (pinfunction "63_63") (pintype "passive"))
      (node (ref "rPI1") (pin "164") (pinfunction "HDMI1_CLK_P_164") (pintype "passive"))
      (node (ref "rxPI1") (pin "164") (pinfunction "HDMI1_CLK_P_164") (pintype "passive"))
    )
    (net (code "19") (name "HDMI1_HOTPLUG") (class "Default")
      (node (ref "H2") (pin "43") (pinfunction "43_43") (pintype "passive"))
      (node (ref "HB") (pin "44") (pinfunction "44_44") (pintype "passive"))
      (node (ref "rPI1") (pin "143") (pinfunction "HDMI1_HOTPLUG_143") (pintype "passive"))
      (node (ref "rxPI1") (pin "143") (pinfunction "HDMI1_HOTPLUG_143") (pintype "passive"))
    )
    (net (code "20") (name "HDMI1_SCL") (class "Default")
      (node (ref "H2") (pin "47") (pinfunction "47_47") (pintype "passive"))
      (node (ref "HB") (pin "48") (pinfunction "48_48") (pintype "passive"))
      (node (ref "rPI1") (pin "147") (pinfunction "HDMI1_SCL_147") (pintype "passive"))
      (node (ref "rxPI1") (pin "147") (pinfunction "HDMI1_SCL_147") (pintype "passive"))
    )
    (net (code "21") (name "HDMI1_SDA") (class "Default")
      (node (ref "H2") (pin "45") (pinfunction "45_45") (pintype "passive"))
      (node (ref "HB") (pin "46") (pinfunction "46_46") (pintype "passive"))
      (node (ref "rPI1") (pin "145") (pinfunction "HDMI1_SDA_145") (pintype "passive"))
      (node (ref "rxPI1") (pin "145") (pinfunction "HDMI1_SDA_145") (pintype "passive"))
    )
    (net (code "22") (name "HDMI1_TX0_N") (class "Default")
      (node (ref "H2") (pin "60") (pinfunction "60_60") (pintype "passive"))
      (node (ref "HB") (pin "59") (pinfunction "59_59") (pintype "passive"))
      (node (ref "rPI1") (pin "160") (pinfunction "HDMI1_TX0_N_160") (pintype "passive"))
      (node (ref "rxPI1") (pin "160") (pinfunction "HDMI1_TX0_N_160") (pintype "passive"))
    )
    (net (code "23") (name "HDMI1_TX0_P") (class "Default")
      (node (ref "H2") (pin "58") (pinfunction "58_58") (pintype "passive"))
      (node (ref "HB") (pin "57") (pinfunction "57_57") (pintype "passive"))
      (node (ref "rPI1") (pin "158") (pinfunction "HDMI1_TX0_P_158") (pintype "passive"))
      (node (ref "rxPI1") (pin "158") (pinfunction "HDMI1_TX0_P_158") (pintype "passive"))
    )
    (net (code "24") (name "HDMI1_TX1_N") (class "Default")
      (node (ref "H2") (pin "54") (pinfunction "54_54") (pintype "passive"))
      (node (ref "HB") (pin "53") (pinfunction "53_53") (pintype "passive"))
      (node (ref "rPI1") (pin "154") (pinfunction "HDMI1_TX1_N_154") (pintype "passive"))
      (node (ref "rxPI1") (pin "154") (pinfunction "HDMI1_TX1_N_154") (pintype "passive"))
    )
    (net (code "25") (name "HDMI1_TX1_P") (class "Default")
      (node (ref "H2") (pin "52") (pinfunction "52_52") (pintype "passive"))
      (node (ref "HB") (pin "51") (pinfunction "51_51") (pintype "passive"))
      (node (ref "rPI1") (pin "152") (pinfunction "HDMI1_TX1_P_152") (pintype "passive"))
      (node (ref "rxPI1") (pin "152") (pinfunction "HDMI1_TX1_P_152") (pintype "passive"))
    )
    (net (code "26") (name "HDMI1_TX2_N") (class "Default")
      (node (ref "H2") (pin "48") (pinfunction "48_48") (pintype "passive"))
      (node (ref "HB") (pin "47") (pinfunction "47_47") (pintype "passive"))
      (node (ref "rPI1") (pin "148") (pinfunction "HDMI1_TX2_N_148") (pintype "passive"))
      (node (ref "rxPI1") (pin "148") (pinfunction "HDMI1_TX2_N_148") (pintype "passive"))
    )
    (net (code "27") (name "HDMI1_TX2_P") (class "Default")
      (node (ref "H2") (pin "46") (pinfunction "46_46") (pintype "passive"))
      (node (ref "HB") (pin "45") (pinfunction "45_45") (pintype "passive"))
      (node (ref "rPI1") (pin "146") (pinfunction "HDMI1_TX2_P_146") (pintype "passive"))
      (node (ref "rxPI1") (pin "146") (pinfunction "HDMI1_TX2_P_146") (pintype "passive"))
    )
    (net (code "28") (name "I2C_SCL") (class "Default")
      (node (ref "J3") (pin "72") (pinfunction "72_72") (pintype "passive"))
      (node (ref "U1") (pin "6") (pinfunction "SCL_6") (pintype "input"))
      (node (ref "rxPI1") (pin "271") (pinfunction "I2C6_SCL_M3_271") (pintype "passive"))
    )
    (net (code "29") (name "I2C_SDA") (class "Default")
      (node (ref "J3") (pin "70") (pinfunction "70_70") (pintype "passive"))
      (node (ref "U1") (pin "7") (pinfunction "SDA_7") (pintype "bidirectional"))
      (node (ref "rxPI1") (pin "269") (pinfunction "I2C6_SDA_M3_269") (pintype "passive"))
    )
    (net (code "30") (name "Net-(D1-I{slash}O1-Pad1)") (class "Default")
      (node (ref "D1") (pin "1") (pinfunction "I/O1_1") (pintype "bidirectional"))
      (node (ref "L1") (pin "4") (pinfunction "4_4") (pintype "passive"))
    )
    (net (code "31") (name "Net-(D1-I{slash}O2-Pad3)") (class "Default")
      (node (ref "D1") (pin "3") (pinfunction "I/O2_3") (pintype "bidirectional"))
      (node (ref "L1") (pin "3") (pinfunction "3_3") (pintype "passive"))
    )
    (net (code "32") (name "Net-(H1-Pad59)") (class "Default")
      (node (ref "H1") (pin "59") (pinfunction "59_59") (pintype "passive"))
      (node (ref "HA") (pin "60") (pinfunction "60_60") (pintype "passive"))
      (node (ref "rPI1") (pin "59") (pinfunction "GND_59") (pintype "passive"))
      (node (ref "rxPI1") (pin "59") (pinfunction "GND_59") (pintype "passive"))
    )
    (net (code "33") (name "Net-(H1-Pad86)") (class "Default")
      (node (ref "H1") (pin "86") (pinfunction "86_86") (pintype "passive"))
      (node (ref "HA") (pin "85") (pinfunction "85_85") (pintype "passive"))
      (node (ref "rPI1") (pin "86") (pinfunction "+3.3v_(Output)_86") (pintype "passive"))
      (node (ref "rxPI1") (pin "86") (pinfunction "+3.3v_(Output)_86") (pintype "passive"))
    )
    (net (code "34") (name "Net-(H1-Pad88)") (class "Default")
      (node (ref "H1") (pin "88") (pinfunction "88_88") (pintype "passive"))
      (node (ref "HA") (pin "87") (pinfunction "87_87") (pintype "passive"))
      (node (ref "rPI1") (pin "88") (pinfunction "+1.8v_(Output)_88") (pintype "passive"))
      (node (ref "rxPI1") (pin "88") (pinfunction "+1.8v_(Output)_88") (pintype "passive"))
    )
    (net (code "35") (name "Net-(H1-Pad90)") (class "Default")
      (node (ref "H1") (pin "90") (pinfunction "90_90") (pintype "passive"))
      (node (ref "HA") (pin "89") (pinfunction "89_89") (pintype "passive"))
      (node (ref "rPI1") (pin "90") (pinfunction "+1.8v_(Output)_90") (pintype "passive"))
      (node (ref "rxPI1") (pin "90") (pinfunction "+1.8v_(Output)_90") (pintype "passive"))
    )
    (net (code "36") (name "Net-(J3-Pad15)") (class "Default")
      (node (ref "J3") (pin "15") (pinfunction "15_15") (pintype "passive"))
      (node (ref "rxPI1") (pin "216") (pinfunction "nc_216") (pintype "passive"))
    )
    (net (code "37") (name "Net-(J3-Pad34)") (class "Default")
      (node (ref "J3") (pin "34") (pinfunction "34_34") (pintype "passive"))
      (node (ref "rxPI1") (pin "233") (pinfunction "nc_233") (pintype "passive"))
    )
    (net (code "38") (name "Net-(J3-Pad36)") (class "Default")
      (node (ref "J3") (pin "36") (pinfunction "36_36") (pintype "passive"))
      (node (ref "rxPI1") (pin "235") (pinfunction "nc_235") (pintype "passive"))
    )
    (net (code "39") (name "Net-(J3-Pad49)") (class "Default")
      (node (ref "J3") (pin "49") (pinfunction "49_49") (pintype "passive"))
      (node (ref "rxPI1") (pin "250") (pinfunction "nc_250") (pintype "passive"))
    )
    (net (code "40") (name "Net-(J3-Pad51)") (class "Default")
      (node (ref "J3") (pin "51") (pinfunction "51_51") (pintype "passive"))
      (node (ref "rxPI1") (pin "252") (pinfunction "nc_252") (pintype "passive"))
    )
    (net (code "41") (name "Net-(J3-Pad53)") (class "Default")
      (node (ref "J3") (pin "53") (pinfunction "53_53") (pintype "passive"))
      (node (ref "rxPI1") (pin "254") (pinfunction "nc_254") (pintype "passive"))
    )
    (net (code "42") (name "Net-(J3-Pad57)") (class "Default")
      (node (ref "J3") (pin "57") (pinfunction "57_57") (pintype "passive"))
      (node (ref "rxPI1") (pin "258") (pinfunction "nc_258") (pintype "passive"))
    )
    (net (code "43") (name "Net-(J3-Pad59)") (class "Default")
      (node (ref "J3") (pin "59") (pinfunction "59_59") (pintype "passive"))
      (node (ref "rxPI1") (pin "260") (pinfunction "nc_260") (pintype "passive"))
    )
    (net (code "44") (name "Net-(J3-Pad63)") (class "Default")
      (node (ref "J3") (pin "63") (pinfunction "63_63") (pintype "passive"))
      (node (ref "rxPI1") (pin "264") (pinfunction "nc_264") (pintype "passive"))
    )
    (net (code "45") (name "Net-(J3-Pad65)") (class "Default")
      (node (ref "J3") (pin "65") (pinfunction "65_65") (pintype "passive"))
      (node (ref "rxPI1") (pin "266") (pinfunction "nc_266") (pintype "passive"))
    )
    (net (code "46") (name "Net-(J3-Pad69)") (class "Default")
      (node (ref "J3") (pin "69") (pinfunction "69_69") (pintype "passive"))
      (node (ref "rxPI1") (pin "270") (pinfunction "nc_270") (pintype "passive"))
    )
    (net (code "47") (name "Net-(J3-Pad77)") (class "Default")
      (node (ref "J3") (pin "77") (pinfunction "77_77") (pintype "passive"))
      (node (ref "rxPI1") (pin "278") (pinfunction "nc_278") (pintype "passive"))
    )
    (net (code "48") (name "Net-(J3-Pad79)") (class "Default")
      (node (ref "J3") (pin "79") (pinfunction "79_79") (pintype "passive"))
      (node (ref "rxPI1") (pin "280") (pinfunction "nc_280") (pintype "passive"))
    )
    (net (code "49") (name "Net-(J3-Pad81)") (class "Default")
      (node (ref "J3") (pin "81") (pinfunction "81_81") (pintype "passive"))
      (node (ref "rxPI1") (pin "282") (pinfunction "nc_282") (pintype "passive"))
    )
    (net (code "50") (name "Net-(J3-Pad83)") (class "Default")
      (node (ref "J3") (pin "83") (pinfunction "83_83") (pintype "passive"))
      (node (ref "rxPI1") (pin "284") (pinfunction "nc_284") (pintype "passive"))
    )
    (net (code "51") (name "Net-(J3-Pad85)") (class "Default")
      (node (ref "J3") (pin "85") (pinfunction "85_85") (pintype "passive"))
      (node (ref "rxPI1") (pin "286") (pinfunction "nc_286") (pintype "passive"))
    )
    (net (code "52") (name "Net-(J3-Pad87)") (class "Default")
      (node (ref "J3") (pin "87") (pinfunction "87_87") (pintype "passive"))
      (node (ref "rxPI1") (pin "288") (pinfunction "nc_288") (pintype "passive"))
    )
    (net (code "53") (name "Net-(J3-Pad89)") (class "Default")
      (node (ref "J3") (pin "89") (pinfunction "89_89") (pintype "passive"))
      (node (ref "rxPI1") (pin "290") (pinfunction "nc_290") (pintype "passive"))
    )
    (net (code "54") (name "Net-(J3-Pad92)") (class "Default")
      (node (ref "J3") (pin "92") (pinfunction "92_92") (pintype "passive"))
      (node (ref "rxPI1") (pin "291") (pinfunction "nc_291") (pintype "passive"))
    )
    (net (code "55") (name "Net-(rPI1A-BT_nDisable)") (class "Default")
      (node (ref "H1") (pin "91") (pinfunction "91_91") (pintype "passive"))
      (node (ref "HA") (pin "92") (pinfunction "92_92") (pintype "passive"))
      (node (ref "rPI1") (pin "91") (pinfunction "BT_nDisable_91") (pintype "passive"))
      (node (ref "rxPI1") (pin "91") (pinfunction "BT_nDisable_91") (pintype "passive"))
    )
    (net (code "56") (name "Net-(rPI1A-CAM_GPIO1)") (class "Default")
      (node (ref "H1") (pin "100") (pinfunction "100_100") (pintype "passive"))
      (node (ref "HA") (pin "99") (pinfunction "99_99") (pintype "passive"))
      (node (ref "rPI1") (pin "100") (pinfunction "CAM_GPIO1_100") (pintype "passive"))
      (node (ref "rxPI1") (pin "100") (pinfunction "nEXTRST_100") (pintype "passive"))
    )
    (net (code "57") (name "Net-(rPI1A-CC1)") (class "Default")
      (node (ref "H1") (pin "94") (pinfunction "94_94") (pintype "passive"))
      (node (ref "HA") (pin "93") (pinfunction "93_93") (pintype "passive"))
      (node (ref "rPI1") (pin "94") (pinfunction "CC1_94") (pintype "passive"))
      (node (ref "rxPI1") (pin "94") (pinfunction "AnalogIP0_94") (pintype "passive"))
    )
    (net (code "58") (name "Net-(rPI1A-CC2)") (class "Default")
      (node (ref "H1") (pin "96") (pinfunction "96_96") (pintype "passive"))
      (node (ref "HA") (pin "95") (pinfunction "95_95") (pintype "passive"))
      (node (ref "rPI1") (pin "96") (pinfunction "CC2_96") (pintype "passive"))
      (node (ref "rxPI1") (pin "96") (pinfunction "AnalogIP1_96") (pintype "passive"))
    )
    (net (code "59") (name "Net-(rPI1A-Camera_GPIO)") (class "Default")
      (node (ref "H1") (pin "97") (pinfunction "97_97") (pintype "passive"))
      (node (ref "HA") (pin "98") (pinfunction "98_98") (pintype "passive"))
      (node (ref "rPI1") (pin "97") (pinfunction "Camera_GPIO_97") (pintype "passive"))
      (node (ref "rxPI1") (pin "97") (pinfunction "Camera_GPIO_97") (pintype "passive"))
    )
    (net (code "60") (name "Net-(rPI1A-EEPROM_nWP)") (class "Default")
      (node (ref "H1") (pin "20") (pinfunction "20_20") (pintype "passive"))
      (node (ref "HA") (pin "19") (pinfunction "19_19") (pintype "passive"))
      (node (ref "rPI1") (pin "20") (pinfunction "EEPROM_nWP_20") (pintype "passive"))
      (node (ref "rxPI1") (pin "20") (pinfunction "EEPROM_nWP_20") (pintype "passive"))
    )
    (net (code "61") (name "Net-(rPI1A-Ethernet_Pair0_N)") (class "Default")
      (node (ref "H1") (pin "10") (pinfunction "10_10") (pintype "passive"))
      (node (ref "HA") (pin "9") (pinfunction "9_9") (pintype "passive"))
      (node (ref "rPI1") (pin "10") (pinfunction "Ethernet_Pair0_N_10") (pintype "passive"))
      (node (ref "rxPI1") (pin "10") (pinfunction "Ethernet_Pair0_N_10") (pintype "passive"))
    )
    (net (code "62") (name "Net-(rPI1A-Ethernet_Pair0_P)") (class "Default")
      (node (ref "H1") (pin "12") (pinfunction "12_12") (pintype "passive"))
      (node (ref "HA") (pin "11") (pinfunction "11_11") (pintype "passive"))
      (node (ref "rPI1") (pin "12") (pinfunction "Ethernet_Pair0_P_12") (pintype "passive"))
      (node (ref "rxPI1") (pin "12") (pinfunction "Ethernet_Pair0_P_12") (pintype "passive"))
    )
    (net (code "63") (name "Net-(rPI1A-Ethernet_Pair1_N)") (class "Default")
      (node (ref "H1") (pin "6") (pinfunction "6_6") (pintype "passive"))
      (node (ref "HA") (pin "5") (pinfunction "5_5") (pintype "passive"))
      (node (ref "rPI1") (pin "6") (pinfunction "Ethernet_Pair1_N_6") (pintype "passive"))
      (node (ref "rxPI1") (pin "6") (pinfunction "Ethernet_Pair1_N_6") (pintype "passive"))
    )
    (net (code "64") (name "Net-(rPI1A-Ethernet_Pair1_P)") (class "Default")
      (node (ref "H1") (pin "4") (pinfunction "4_4") (pintype "passive"))
      (node (ref "HA") (pin "3") (pinfunction "3_3") (pintype "passive"))
      (node (ref "rPI1") (pin "4") (pinfunction "Ethernet_Pair1_P_4") (pintype "passive"))
      (node (ref "rxPI1") (pin "4") (pinfunction "Ethernet_Pair1_P_4") (pintype "passive"))
    )
    (net (code "65") (name "Net-(rPI1A-Ethernet_Pair2_N)") (class "Default")
      (node (ref "H1") (pin "9") (pinfunction "9_9") (pintype "passive"))
      (node (ref "HA") (pin "10") (pinfunction "10_10") (pintype "passive"))
      (node (ref "rPI1") (pin "9") (pinfunction "Ethernet_Pair2_N_9") (pintype "passive"))
      (node (ref "rxPI1") (pin "9") (pinfunction "Ethernet_Pair2_N_9") (pintype "passive"))
    )
    (net (code "66") (name "Net-(rPI1A-Ethernet_Pair2_P)") (class "Default")
      (node (ref "H1") (pin "11") (pinfunction "11_11") (pintype "passive"))
      (node (ref "HA") (pin "12") (pinfunction "12_12") (pintype "passive"))
      (node (ref "rPI1") (pin "11") (pinfunction "Ethernet_Pair2_P_11") (pintype "passive"))
      (node (ref "rxPI1") (pin "11") (pinfunction "Ethernet_Pair2_P_11") (pintype "passive"))
    )
    (net (code "67") (name "Net-(rPI1A-Ethernet_Pair3_N)") (class "Default")
      (node (ref "H1") (pin "5") (pinfunction "5_5") (pintype "passive"))
      (node (ref "HA") (pin "6") (pinfunction "6_6") (pintype "passive"))
      (node (ref "rPI1") (pin "5") (pinfunction "Ethernet_Pair3_N_5") (pintype "passive"))
      (node (ref "rxPI1") (pin "5") (pinfunction "Ethernet_Pair3_N_5") (pintype "passive"))
    )
    (net (code "68") (name "Net-(rPI1A-Ethernet_Pair3_P)") (class "Default")
      (node (ref "H1") (pin "3") (pinfunction "3_3") (pintype "passive"))
      (node (ref "HA") (pin "4") (pinfunction "4_4") (pintype "passive"))
      (node (ref "rPI1") (pin "3") (pinfunction "Ethernet_Pair3_P_3") (pintype "passive"))
      (node (ref "rxPI1") (pin "3") (pinfunction "Ethernet_Pair3_P_3") (pintype "passive"))
    )
    (net (code "69") (name "Net-(rPI1A-Ethernet_SYNC_IN(1.8v))") (class "Default")
      (node (ref "H1") (pin "16") (pinfunction "16_16") (pintype "passive"))
      (node (ref "HA") (pin "15") (pinfunction "15_15") (pintype "passive"))
      (node (ref "rPI1") (pin "16") (pinfunction "Ethernet_SYNC_IN(1.8v)_16") (pintype "passive"))
      (node (ref "rxPI1") (pin "16") (pinfunction "Ethernet_SYNC_IN(1.8v)_16") (pintype "passive"))
    )
    (net (code "70") (name "Net-(rPI1A-Ethernet_SYNC_OUT(1.8v))") (class "Default")
      (node (ref "H1") (pin "18") (pinfunction "18_18") (pintype "passive"))
      (node (ref "HA") (pin "17") (pinfunction "17_17") (pintype "passive"))
      (node (ref "rPI1") (pin "18") (pinfunction "Ethernet_SYNC_OUT(1.8v)_18") (pintype "passive"))
      (node (ref "rxPI1") (pin "18") (pinfunction "Ethernet_SYNC_OUT(1.8v)_18") (pintype "passive"))
    )
    (net (code "71") (name "Net-(rPI1A-Ethernet_nLED2(3.3v))") (class "Default")
      (node (ref "H1") (pin "17") (pinfunction "17_17") (pintype "passive"))
      (node (ref "HA") (pin "18") (pinfunction "18_18") (pintype "passive"))
      (node (ref "rPI1") (pin "17") (pinfunction "Ethernet_nLED2(3.3v)_17") (pintype "passive"))
      (node (ref "rxPI1") (pin "17") (pinfunction "Ethernet_nLED2(3.3v)_17") (pintype "passive"))
    )
    (net (code "72") (name "Net-(rPI1A-Ethernet_nLED3(3.3v))") (class "Default")
      (node (ref "H1") (pin "15") (pinfunction "15_15") (pintype "passive"))
      (node (ref "HA") (pin "16") (pinfunction "16_16") (pintype "passive"))
      (node (ref "rPI1") (pin "15") (pinfunction "Ethernet_nLED3(3.3v)_15") (pintype "passive"))
      (node (ref "rxPI1") (pin "15") (pinfunction "Ethernet_nLED3(3.3v)_15") (pintype "passive"))
    )
    (net (code "73") (name "Net-(rPI1A-FAN_PWM)") (class "Default")
      (node (ref "H1") (pin "19") (pinfunction "19_19") (pintype "passive"))
      (node (ref "HA") (pin "20") (pinfunction "20_20") (pintype "passive"))
      (node (ref "rPI1") (pin "19") (pinfunction "FAN_PWM_19") (pintype "passive"))
      (node (ref "rxPI1") (pin "19") (pinfunction "Ethernet_nLED1(3.3v)_19") (pintype "passive"))
    )
    (net (code "74") (name "Net-(rPI1A-GPIO2)") (class "Default")
      (node (ref "H1") (pin "58") (pinfunction "58_58") (pintype "passive"))
      (node (ref "HA") (pin "57") (pinfunction "57_57") (pintype "passive"))
      (node (ref "rPI1") (pin "58") (pinfunction "GPIO2_58") (pintype "passive"))
      (node (ref "rxPI1") (pin "58") (pinfunction "GPIO2_58") (pintype "passive"))
    )
    (net (code "75") (name "Net-(rPI1A-GPIO3)") (class "Default")
      (node (ref "H1") (pin "56") (pinfunction "56_56") (pintype "passive"))
      (node (ref "HA") (pin "55") (pinfunction "55_55") (pintype "passive"))
      (node (ref "rPI1") (pin "56") (pinfunction "GPIO3_56") (pintype "passive"))
      (node (ref "rxPI1") (pin "56") (pinfunction "GPIO3_56") (pintype "passive"))
    )
    (net (code "76") (name "Net-(rPI1A-GPIO4)") (class "Default")
      (node (ref "H1") (pin "54") (pinfunction "54_54") (pintype "passive"))
      (node (ref "HA") (pin "53") (pinfunction "53_53") (pintype "passive"))
      (node (ref "rPI1") (pin "54") (pinfunction "GPIO4_54") (pintype "passive"))
      (node (ref "rxPI1") (pin "54") (pinfunction "GPIO4_54") (pintype "passive"))
    )
    (net (code "77") (name "Net-(rPI1A-GPIO5)") (class "Default")
      (node (ref "H1") (pin "34") (pinfunction "34_34") (pintype "passive"))
      (node (ref "HA") (pin "33") (pinfunction "33_33") (pintype "passive"))
      (node (ref "rPI1") (pin "34") (pinfunction "GPIO5_34") (pintype "passive"))
      (node (ref "rxPI1") (pin "34") (pinfunction "GPIO5_34") (pintype "passive"))
    )
    (net (code "78") (name "Net-(rPI1A-GPIO6)") (class "Default")
      (node (ref "H1") (pin "30") (pinfunction "30_30") (pintype "passive"))
      (node (ref "HA") (pin "29") (pinfunction "29_29") (pintype "passive"))
      (node (ref "rPI1") (pin "30") (pinfunction "GPIO6_30") (pintype "passive"))
      (node (ref "rxPI1") (pin "30") (pinfunction "GPIO6_30") (pintype "passive"))
    )
    (net (code "79") (name "Net-(rPI1A-GPIO7)") (class "Default")
      (node (ref "H1") (pin "37") (pinfunction "37_37") (pintype "passive"))
      (node (ref "HA") (pin "38") (pinfunction "38_38") (pintype "passive"))
      (node (ref "rPI1") (pin "37") (pinfunction "GPIO7_37") (pintype "passive"))
      (node (ref "rxPI1") (pin "37") (pinfunction "GPIO7_37") (pintype "passive"))
    )
    (net (code "80") (name "Net-(rPI1A-GPIO8)") (class "Default")
      (node (ref "H1") (pin "39") (pinfunction "39_39") (pintype "passive"))
      (node (ref "HA") (pin "40") (pinfunction "40_40") (pintype "passive"))
      (node (ref "rPI1") (pin "39") (pinfunction "GPIO8_39") (pintype "passive"))
      (node (ref "rxPI1") (pin "39") (pinfunction "GPIO8_39") (pintype "passive"))
    )
    (net (code "81") (name "Net-(rPI1A-GPIO9)") (class "Default")
      (node (ref "H1") (pin "40") (pinfunction "40_40") (pintype "passive"))
      (node (ref "HA") (pin "39") (pinfunction "39_39") (pintype "passive"))
      (node (ref "rPI1") (pin "40") (pinfunction "GPIO9_40") (pintype "passive"))
      (node (ref "rxPI1") (pin "40") (pinfunction "GPIO9_40") (pintype "passive"))
    )
    (net (code "82") (name "Net-(rPI1A-GPIO10)") (class "Default")
      (node (ref "H1") (pin "44") (pinfunction "44_44") (pintype "passive"))
      (node (ref "HA") (pin "43") (pinfunction "43_43") (pintype "passive"))
      (node (ref "rPI1") (pin "44") (pinfunction "GPIO10_44") (pintype "passive"))
      (node (ref "rxPI1") (pin "44") (pinfunction "GPIO10_44") (pintype "passive"))
    )
    (net (code "83") (name "Net-(rPI1A-GPIO11)") (class "Default")
      (node (ref "H1") (pin "38") (pinfunction "38_38") (pintype "passive"))
      (node (ref "HA") (pin "37") (pinfunction "37_37") (pintype "passive"))
      (node (ref "rPI1") (pin "38") (pinfunction "GPIO11_38") (pintype "passive"))
      (node (ref "rxPI1") (pin "38") (pinfunction "GPIO11_38") (pintype "passive"))
    )
    (net (code "84") (name "Net-(rPI1A-GPIO12)") (class "Default")
      (node (ref "H1") (pin "31") (pinfunction "31_31") (pintype "passive"))
      (node (ref "HA") (pin "32") (pinfunction "32_32") (pintype "passive"))
      (node (ref "rPI1") (pin "31") (pinfunction "GPIO12_31") (pintype "passive"))
      (node (ref "rxPI1") (pin "31") (pinfunction "GPIO12_31") (pintype "passive"))
    )
    (net (code "85") (name "Net-(rPI1A-GPIO13)") (class "Default")
      (node (ref "H1") (pin "28") (pinfunction "28_28") (pintype "passive"))
      (node (ref "HA") (pin "27") (pinfunction "27_27") (pintype "passive"))
      (node (ref "rPI1") (pin "28") (pinfunction "GPIO13_28") (pintype "passive"))
      (node (ref "rxPI1") (pin "28") (pinfunction "GPIO13_28") (pintype "passive"))
    )
    (net (code "86") (name "Net-(rPI1A-GPIO14)") (class "Default")
      (node (ref "H1") (pin "55") (pinfunction "55_55") (pintype "passive"))
      (node (ref "HA") (pin "56") (pinfunction "56_56") (pintype "passive"))
      (node (ref "rPI1") (pin "55") (pinfunction "GPIO14_55") (pintype "passive"))
      (node (ref "rxPI1") (pin "55") (pinfunction "GPIO14_55") (pintype "passive"))
    )
    (net (code "87") (name "Net-(rPI1A-GPIO15)") (class "Default")
      (node (ref "H1") (pin "51") (pinfunction "51_51") (pintype "passive"))
      (node (ref "HA") (pin "52") (pinfunction "52_52") (pintype "passive"))
      (node (ref "rPI1") (pin "51") (pinfunction "GPIO15_51") (pintype "passive"))
      (node (ref "rxPI1") (pin "51") (pinfunction "GPIO15_51") (pintype "passive"))
    )
    (net (code "88") (name "Net-(rPI1A-GPIO16)") (class "Default")
      (node (ref "H1") (pin "29") (pinfunction "29_29") (pintype "passive"))
      (node (ref "HA") (pin "30") (pinfunction "30_30") (pintype "passive"))
      (node (ref "rPI1") (pin "29") (pinfunction "GPIO16_29") (pintype "passive"))
      (node (ref "rxPI1") (pin "29") (pinfunction "GPIO16_29") (pintype "passive"))
    )
    (net (code "89") (name "Net-(rPI1A-GPIO17)") (class "Default")
      (node (ref "H1") (pin "50") (pinfunction "50_50") (pintype "passive"))
      (node (ref "HA") (pin "49") (pinfunction "49_49") (pintype "passive"))
      (node (ref "rPI1") (pin "50") (pinfunction "GPIO17_50") (pintype "passive"))
      (node (ref "rxPI1") (pin "50") (pinfunction "GPIO17_50") (pintype "passive"))
    )
    (net (code "90") (name "Net-(rPI1A-GPIO18)") (class "Default")
      (node (ref "H1") (pin "49") (pinfunction "49_49") (pintype "passive"))
      (node (ref "HA") (pin "50") (pinfunction "50_50") (pintype "passive"))
      (node (ref "rPI1") (pin "49") (pinfunction "GPIO18_49") (pintype "passive"))
      (node (ref "rxPI1") (pin "49") (pinfunction "GPIO18_49") (pintype "passive"))
    )
    (net (code "91") (name "Net-(rPI1A-GPIO19)") (class "Default")
      (node (ref "H1") (pin "26") (pinfunction "26_26") (pintype "passive"))
      (node (ref "HA") (pin "25") (pinfunction "25_25") (pintype "passive"))
      (node (ref "rPI1") (pin "26") (pinfunction "GPIO19_26") (pintype "passive"))
      (node (ref "rxPI1") (pin "26") (pinfunction "GPIO19_26") (pintype "passive"))
    )
    (net (code "92") (name "Net-(rPI1A-GPIO20)") (class "Default")
      (node (ref "H1") (pin "27") (pinfunction "27_27") (pintype "passive"))
      (node (ref "HA") (pin "28") (pinfunction "28_28") (pintype "passive"))
      (node (ref "rPI1") (pin "27") (pinfunction "GPIO20_27") (pintype "passive"))
      (node (ref "rxPI1") (pin "27") (pinfunction "GPIO20_27") (pintype "passive"))
    )
    (net (code "93") (name "Net-(rPI1A-GPIO21)") (class "Default")
      (node (ref "H1") (pin "25") (pinfunction "25_25") (pintype "passive"))
      (node (ref "HA") (pin "26") (pinfunction "26_26") (pintype "passive"))
      (node (ref "rPI1") (pin "25") (pinfunction "GPIO21_25") (pintype "passive"))
      (node (ref "rxPI1") (pin "25") (pinfunction "GPIO21_25") (pintype "passive"))
    )
    (net (code "94") (name "Net-(rPI1A-GPIO22)") (class "Default")
      (node (ref "H1") (pin "46") (pinfunction "46_46") (pintype "passive"))
      (node (ref "HA") (pin "45") (pinfunction "45_45") (pintype "passive"))
      (node (ref "rPI1") (pin "46") (pinfunction "GPIO22_46") (pintype "passive"))
      (node (ref "rxPI1") (pin "46") (pinfunction "GPIO22_46") (pintype "passive"))
    )
    (net (code "95") (name "Net-(rPI1A-GPIO23)") (class "Default")
      (node (ref "H1") (pin "47") (pinfunction "47_47") (pintype "passive"))
      (node (ref "HA") (pin "48") (pinfunction "48_48") (pintype "passive"))
      (node (ref "rPI1") (pin "47") (pinfunction "GPIO23_47") (pintype "passive"))
      (node (ref "rxPI1") (pin "47") (pinfunction "GPIO23_47") (pintype "passive"))
    )
    (net (code "96") (name "Net-(rPI1A-GPIO24)") (class "Default")
      (node (ref "H1") (pin "45") (pinfunction "45_45") (pintype "passive"))
      (node (ref "HA") (pin "46") (pinfunction "46_46") (pintype "passive"))
      (node (ref "rPI1") (pin "45") (pinfunction "GPIO24_45") (pintype "passive"))
      (node (ref "rxPI1") (pin "45") (pinfunction "GPIO24_45") (pintype "passive"))
    )
    (net (code "97") (name "Net-(rPI1A-GPIO25)") (class "Default")
      (node (ref "H1") (pin "41") (pinfunction "41_41") (pintype "passive"))
      (node (ref "HA") (pin "42") (pinfunction "42_42") (pintype "passive"))
      (node (ref "rPI1") (pin "41") (pinfunction "GPIO25_41") (pintype "passive"))
      (node (ref "rxPI1") (pin "41") (pinfunction "GPIO25_41") (pintype "passive"))
    )
    (net (code "98") (name "Net-(rPI1A-GPIO26)") (class "Default")
      (node (ref "H1") (pin "24") (pinfunction "24_24") (pintype "passive"))
      (node (ref "HA") (pin "23") (pinfunction "23_23") (pintype "passive"))
      (node (ref "rPI1") (pin "24") (pinfunction "GPIO26_24") (pintype "passive"))
      (node (ref "rxPI1") (pin "24") (pinfunction "GPIO26_24") (pintype "passive"))
    )
    (net (code "99") (name "Net-(rPI1A-GPIO27)") (class "Default")
      (node (ref "H1") (pin "48") (pinfunction "48_48") (pintype "passive"))
      (node (ref "HA") (pin "47") (pinfunction "47_47") (pintype "passive"))
      (node (ref "rPI1") (pin "48") (pinfunction "GPIO27_48") (pintype "passive"))
      (node (ref "rxPI1") (pin "48") (pinfunction "GPIO27_48") (pintype "passive"))
    )
    (net (code "100") (name "Net-(rPI1A-GPIO_VREF(1.8v{slash}3.3v_Input))") (class "Default")
      (node (ref "H1") (pin "78") (pinfunction "78_78") (pintype "passive"))
      (node (ref "HA") (pin "77") (pinfunction "77_77") (pintype "passive"))
      (node (ref "rPI1") (pin "78") (pinfunction "GPIO_VREF(1.8v/3.3v_Input)_78") (pintype "passive"))
      (node (ref "rxPI1") (pin "78") (pinfunction "GPIO_VREF(1.8v/3.3v_Input)_78") (pintype "passive"))
    )
    (net (code "101") (name "Net-(rPI1A-Global_EN)") (class "Default")
      (node (ref "H1") (pin "99") (pinfunction "99_99") (pintype "passive"))
      (node (ref "HA") (pin "100") (pinfunction "100_100") (pintype "passive"))
      (node (ref "rPI1") (pin "99") (pinfunction "Global_EN_99") (pintype "passive"))
      (node (ref "rxPI1") (pin "99") (pinfunction "Global_EN_99") (pintype "passive"))
    )
    (net (code "102") (name "Net-(rPI1A-ID_SC)") (class "Default")
      (node (ref "H1") (pin "35") (pinfunction "35_35") (pintype "passive"))
      (node (ref "HA") (pin "36") (pinfunction "36_36") (pintype "passive"))
      (node (ref "rPI1") (pin "35") (pinfunction "ID_SC_35") (pintype "passive"))
      (node (ref "rxPI1") (pin "35") (pinfunction "ID_SC_35") (pintype "passive"))
    )
    (net (code "103") (name "Net-(rPI1A-ID_SD)") (class "Default")
      (node (ref "H1") (pin "36") (pinfunction "36_36") (pintype "passive"))
      (node (ref "HA") (pin "35") (pinfunction "35_35") (pintype "passive"))
      (node (ref "rPI1") (pin "36") (pinfunction "ID_SD_36") (pintype "passive"))
      (node (ref "rxPI1") (pin "36") (pinfunction "ID_SD_36") (pintype "passive"))
    )
    (net (code "104") (name "Net-(rPI1A-PI_nLED_Activity)") (class "Default")
      (node (ref "H1") (pin "21") (pinfunction "21_21") (pintype "passive"))
      (node (ref "HA") (pin "22") (pinfunction "22_22") (pintype "passive"))
      (node (ref "rPI1") (pin "21") (pinfunction "PI_nLED_Activity_21") (pintype "passive"))
      (node (ref "rxPI1") (pin "21") (pinfunction "PI_nLED_Activity_21") (pintype "passive"))
    )
    (net (code "105") (name "Net-(rPI1A-RUN_PG)") (class "Default")
      (node (ref "H1") (pin "92") (pinfunction "92_92") (pintype "passive"))
      (node (ref "HA") (pin "91") (pinfunction "91_91") (pintype "passive"))
      (node (ref "rPI1") (pin "92") (pinfunction "RUN_PG_92") (pintype "passive"))
      (node (ref "rxPI1") (pin "92") (pinfunction "RUN_PG_92") (pintype "passive"))
    )
    (net (code "106") (name "Net-(rPI1A-Reserved)") (class "Default")
      (node (ref "H1") (pin "76") (pinfunction "76_76") (pintype "passive"))
      (node (ref "HA") (pin "75") (pinfunction "75_75") (pintype "passive"))
      (node (ref "rPI1") (pin "76") (pinfunction "Reserved_76") (pintype "passive"))
      (node (ref "rxPI1") (pin "76") (pinfunction "Reserved_76") (pintype "passive"))
    )
    (net (code "107") (name "Net-(rPI1A-SCL0)") (class "Default")
      (node (ref "H1") (pin "80") (pinfunction "80_80") (pintype "passive"))
      (node (ref "HA") (pin "79") (pinfunction "79_79") (pintype "passive"))
      (node (ref "rPI1") (pin "80") (pinfunction "SCL0_80") (pintype "passive"))
      (node (ref "rxPI1") (pin "80") (pinfunction "SCL0_80") (pintype "passive"))
    )
    (net (code "108") (name "Net-(rPI1A-SDA0)") (class "Default")
      (node (ref "H1") (pin "82") (pinfunction "82_82") (pintype "passive"))
      (node (ref "HA") (pin "81") (pinfunction "81_81") (pintype "passive"))
      (node (ref "rPI1") (pin "82") (pinfunction "SDA0_82") (pintype "passive"))
      (node (ref "rxPI1") (pin "82") (pinfunction "SDA0_82") (pintype "passive"))
    )
    (net (code "109") (name "Net-(rPI1A-SD_CLK)") (class "Default")
      (node (ref "H1") (pin "57") (pinfunction "57_57") (pintype "passive"))
      (node (ref "HA") (pin "58") (pinfunction "58_58") (pintype "passive"))
      (node (ref "rPI1") (pin "57") (pinfunction "SD_CLK_57") (pintype "passive"))
      (node (ref "rxPI1") (pin "57") (pinfunction "SD_CLK_57") (pintype "passive"))
    )
    (net (code "110") (name "Net-(rPI1A-SD_CMD)") (class "Default")
      (node (ref "H1") (pin "62") (pinfunction "62_62") (pintype "passive"))
      (node (ref "HA") (pin "61") (pinfunction "61_61") (pintype "passive"))
      (node (ref "rPI1") (pin "62") (pinfunction "SD_CMD_62") (pintype "passive"))
      (node (ref "rxPI1") (pin "62") (pinfunction "SD_CMD_62") (pintype "passive"))
    )
    (net (code "111") (name "Net-(rPI1A-SD_DAT0)") (class "Default")
      (node (ref "H1") (pin "63") (pinfunction "63_63") (pintype "passive"))
      (node (ref "HA") (pin "64") (pinfunction "64_64") (pintype "passive"))
      (node (ref "rPI1") (pin "63") (pinfunction "SD_DAT0_63") (pintype "passive"))
      (node (ref "rxPI1") (pin "63") (pinfunction "SD_DAT0_63") (pintype "passive"))
    )
    (net (code "112") (name "Net-(rPI1A-SD_DAT1)") (class "Default")
      (node (ref "H1") (pin "67") (pinfunction "67_67") (pintype "passive"))
      (node (ref "HA") (pin "68") (pinfunction "68_68") (pintype "passive"))
      (node (ref "rPI1") (pin "67") (pinfunction "SD_DAT1_67") (pintype "passive"))
      (node (ref "rxPI1") (pin "67") (pinfunction "SD_DAT1_67") (pintype "passive"))
    )
    (net (code "113") (name "Net-(rPI1A-SD_DAT2)") (class "Default")
      (node (ref "H1") (pin "69") (pinfunction "69_69") (pintype "passive"))
      (node (ref "HA") (pin "70") (pinfunction "70_70") (pintype "passive"))
      (node (ref "rPI1") (pin "69") (pinfunction "SD_DAT2_69") (pintype "passive"))
      (node (ref "rxPI1") (pin "69") (pinfunction "SD_DAT2_69") (pintype "passive"))
    )
    (net (code "114") (name "Net-(rPI1A-SD_DAT3)") (class "Default")
      (node (ref "H1") (pin "61") (pinfunction "61_61") (pintype "passive"))
      (node (ref "HA") (pin "62") (pinfunction "62_62") (pintype "passive"))
      (node (ref "rPI1") (pin "61") (pinfunction "SD_DAT3_61") (pintype "passive"))
      (node (ref "rxPI1") (pin "61") (pinfunction "SD_DAT3_61") (pintype "passive"))
    )
    (net (code "115") (name "Net-(rPI1A-SD_DAT4)") (class "Default")
      (node (ref "H1") (pin "68") (pinfunction "68_68") (pintype "passive"))
      (node (ref "HA") (pin "67") (pinfunction "67_67") (pintype "passive"))
      (node (ref "rPI1") (pin "68") (pinfunction "SD_DAT4_68") (pintype "passive"))
      (node (ref "rxPI1") (pin "68") (pinfunction "SD_DAT4_68") (pintype "passive"))
    )
    (net (code "116") (name "Net-(rPI1A-SD_DAT5)") (class "Default")
      (node (ref "H1") (pin "64") (pinfunction "64_64") (pintype "passive"))
      (node (ref "HA") (pin "63") (pinfunction "63_63") (pintype "passive"))
      (node (ref "rPI1") (pin "64") (pinfunction "SD_DAT5_64") (pintype "passive"))
      (node (ref "rxPI1") (pin "64") (pinfunction "SD_DAT5_64") (pintype "passive"))
    )
    (net (code "117") (name "Net-(rPI1A-SD_DAT6)") (class "Default")
      (node (ref "H1") (pin "72") (pinfunction "72_72") (pintype "passive"))
      (node (ref "HA") (pin "71") (pinfunction "71_71") (pintype "passive"))
      (node (ref "rPI1") (pin "72") (pinfunction "SD_DAT6_72") (pintype "passive"))
      (node (ref "rxPI1") (pin "72") (pinfunction "SD_DAT6_72") (pintype "passive"))
    )
    (net (code "118") (name "Net-(rPI1A-SD_DAT7)") (class "Default")
      (node (ref "H1") (pin "70") (pinfunction "70_70") (pintype "passive"))
      (node (ref "HA") (pin "69") (pinfunction "69_69") (pintype "passive"))
      (node (ref "rPI1") (pin "70") (pinfunction "SD_DAT7_70") (pintype "passive"))
      (node (ref "rxPI1") (pin "70") (pinfunction "SD_DAT7_70") (pintype "passive"))
    )
    (net (code "119") (name "Net-(rPI1A-SD_PWR_ON)") (class "Default")
      (node (ref "H1") (pin "75") (pinfunction "75_75") (pintype "passive"))
      (node (ref "HA") (pin "76") (pinfunction "76_76") (pintype "passive"))
      (node (ref "rPI1") (pin "75") (pinfunction "SD_PWR_ON_75") (pintype "passive"))
      (node (ref "rxPI1") (pin "75") (pinfunction "SD_PWR_ON_75") (pintype "passive"))
    )
    (net (code "120") (name "Net-(rPI1A-SD_VDD_Override)") (class "Default")
      (node (ref "H1") (pin "73") (pinfunction "73_73") (pintype "passive"))
      (node (ref "HA") (pin "74") (pinfunction "74_74") (pintype "passive"))
      (node (ref "rPI1") (pin "73") (pinfunction "SD_VDD_Override_73") (pintype "passive"))
      (node (ref "rxPI1") (pin "73") (pinfunction "SD_VDD_Override_73") (pintype "passive"))
    )
    (net (code "121") (name "Net-(rPI1A-WiFi_nDisable)") (class "Default")
      (node (ref "H1") (pin "89") (pinfunction "89_89") (pintype "passive"))
      (node (ref "HA") (pin "90") (pinfunction "90_90") (pintype "passive"))
      (node (ref "rPI1") (pin "89") (pinfunction "WiFi_nDisable_89") (pintype "passive"))
      (node (ref "rxPI1") (pin "89") (pinfunction "WiFi_nDisable_89") (pintype "passive"))
    )
    (net (code "122") (name "Net-(rPI1A-nPI_LED_PWR)") (class "Default")
      (node (ref "H1") (pin "95") (pinfunction "95_95") (pintype "passive"))
      (node (ref "HA") (pin "96") (pinfunction "96_96") (pintype "passive"))
      (node (ref "rPI1") (pin "95") (pinfunction "nPI_LED_PWR_95") (pintype "passive"))
      (node (ref "rxPI1") (pin "95") (pinfunction "nPI_LED_PWR_95") (pintype "passive"))
    )
    (net (code "123") (name "Net-(rPI1A-nRPIBOOT)") (class "Default")
      (node (ref "H1") (pin "93") (pinfunction "93_93") (pintype "passive"))
      (node (ref "HA") (pin "94") (pinfunction "94_94") (pintype "passive"))
      (node (ref "rPI1") (pin "93") (pinfunction "nRPIBOOT_93") (pintype "passive"))
      (node (ref "rxPI1") (pin "93") (pinfunction "nRPIBOOT_93") (pintype "passive"))
    )
    (net (code "124") (name "Net-(rPI1B-MIPI0_C_N)") (class "Default")
      (node (ref "HB") (pin "28") (pinfunction "28_28") (pintype "passive"))
      (node (ref "rPI1") (pin "127") (pinfunction "MIPI0_C_N_127") (pintype "passive"))
    )
    (net (code "125") (name "Net-(rPI1B-MIPI0_C_P)") (class "Default")
      (node (ref "HB") (pin "30") (pinfunction "30_30") (pintype "passive"))
      (node (ref "rPI1") (pin "129") (pinfunction "MIPI0_C_P_129") (pintype "passive"))
    )
    (net (code "126") (name "Net-(rPI1B-MIPI0_D0_N)") (class "Default")
      (node (ref "HB") (pin "16") (pinfunction "16_16") (pintype "passive"))
      (node (ref "rPI1") (pin "115") (pinfunction "MIPI0_D0_N_115") (pintype "passive"))
    )
    (net (code "127") (name "Net-(rPI1B-MIPI0_D0_P)") (class "Default")
      (node (ref "HB") (pin "18") (pinfunction "18_18") (pintype "passive"))
      (node (ref "rPI1") (pin "117") (pinfunction "MIPI0_D0_P_117") (pintype "passive"))
    )
    (net (code "128") (name "Net-(rPI1B-MIPI0_D1_N)") (class "Default")
      (node (ref "HB") (pin "22") (pinfunction "22_22") (pintype "passive"))
      (node (ref "rPI1") (pin "121") (pinfunction "MIPI0_D1_N_121") (pintype "passive"))
    )
    (net (code "129") (name "Net-(rPI1B-MIPI0_D1_P)") (class "Default")
      (node (ref "HB") (pin "24") (pinfunction "24_24") (pintype "passive"))
      (node (ref "rPI1") (pin "123") (pinfunction "MIPI0_D1_P_123") (pintype "passive"))
    )
    (net (code "130") (name "Net-(rPI1B-MIPI0_D2_N)") (class "Default")
      (node (ref "HB") (pin "34") (pinfunction "34_34") (pintype "passive"))
      (node (ref "rPI1") (pin "133") (pinfunction "MIPI0_D2_N_133") (pintype "passive"))
    )
    (net (code "131") (name "Net-(rPI1B-MIPI0_D2_P)") (class "Default")
      (node (ref "HB") (pin "36") (pinfunction "36_36") (pintype "passive"))
      (node (ref "rPI1") (pin "135") (pinfunction "MIPI0_D2_P_135") (pintype "passive"))
    )
    (net (code "132") (name "Net-(rPI1B-MIPI0_D3_N)") (class "Default")
      (node (ref "HB") (pin "40") (pinfunction "40_40") (pintype "passive"))
      (node (ref "rPI1") (pin "139") (pinfunction "MIPI0_D3_N_139") (pintype "passive"))
    )
    (net (code "133") (name "Net-(rPI1B-MIPI0_D3_P)") (class "Default")
      (node (ref "HB") (pin "42") (pinfunction "42_42") (pintype "passive"))
      (node (ref "rPI1") (pin "141") (pinfunction "MIPI0_D3_P_141") (pintype "passive"))
    )
    (net (code "134") (name "Net-(rPI1B-MIPI1_C_N)") (class "Default")
      (node (ref "HB") (pin "88") (pinfunction "88_88") (pintype "passive"))
      (node (ref "rPI1") (pin "187") (pinfunction "MIPI1_C_N_187") (pintype "passive"))
    )
    (net (code "135") (name "Net-(rPI1B-MIPI1_C_P)") (class "Default")
      (node (ref "HB") (pin "90") (pinfunction "90_90") (pintype "passive"))
      (node (ref "rPI1") (pin "189") (pinfunction "MIPI1_C_P_189") (pintype "passive"))
    )
    (net (code "136") (name "Net-(rPI1B-MIPI1_D0_N)") (class "Default")
      (node (ref "HB") (pin "76") (pinfunction "76_76") (pintype "passive"))
      (node (ref "rPI1") (pin "175") (pinfunction "MIPI1_D0_N_175") (pintype "passive"))
    )
    (net (code "137") (name "Net-(rPI1B-MIPI1_D0_P)") (class "Default")
      (node (ref "HB") (pin "78") (pinfunction "78_78") (pintype "passive"))
      (node (ref "rPI1") (pin "177") (pinfunction "MIPI1_D0_P_177") (pintype "passive"))
    )
    (net (code "138") (name "Net-(rPI1B-MIPI1_D1_N)") (class "Default")
      (node (ref "HB") (pin "82") (pinfunction "82_82") (pintype "passive"))
      (node (ref "rPI1") (pin "181") (pinfunction "MIPI1_D1_N_181") (pintype "passive"))
    )
    (net (code "139") (name "Net-(rPI1B-MIPI1_D1_P)") (class "Default")
      (node (ref "HB") (pin "84") (pinfunction "84_84") (pintype "passive"))
      (node (ref "rPI1") (pin "183") (pinfunction "MIPI1_D1_P_183") (pintype "passive"))
    )
    (net (code "140") (name "Net-(rPI1B-MIPI1_D2_N)") (class "Default")
      (node (ref "HB") (pin "94") (pinfunction "94_94") (pintype "passive"))
      (node (ref "rPI1") (pin "193") (pinfunction "MIPI1_D2_N_193") (pintype "passive"))
    )
    (net (code "141") (name "Net-(rPI1B-MIPI1_D2_P)") (class "Default")
      (node (ref "HB") (pin "96") (pinfunction "96_96") (pintype "passive"))
      (node (ref "rPI1") (pin "195") (pinfunction "MIPI1_D2_P_195") (pintype "passive"))
    )
    (net (code "142") (name "Net-(rPI1B-MIPI1_D3_N)") (class "Default")
      (node (ref "HB") (pin "93") (pinfunction "93_93") (pintype "passive"))
      (node (ref "rPI1") (pin "194") (pinfunction "MIPI1_D3_N_194") (pintype "passive"))
    )
    (net (code "143") (name "Net-(rPI1B-MIPI1_D3_P)") (class "Default")
      (node (ref "HB") (pin "95") (pinfunction "95_95") (pintype "passive"))
      (node (ref "rPI1") (pin "196") (pinfunction "MIPI1_D3_P_196") (pintype "passive"))
    )
    (net (code "144") (name "Net-(rPI1B-VBUS_EN)") (class "Default")
      (node (ref "HB") (pin "12") (pinfunction "12_12") (pintype "passive"))
      (node (ref "rPI1") (pin "111") (pinfunction "VBUS_EN_111") (pintype "passive"))
    )
    (net (code "145") (name "Net-(rxPI1B-CAM0_C_N)") (class "Default")
      (node (ref "H2") (pin "40") (pinfunction "40_40") (pintype "passive"))
      (node (ref "rxPI1") (pin "140") (pinfunction "CAM0_C_N_140") (pintype "passive"))
    )
    (net (code "146") (name "Net-(rxPI1B-CAM0_C_P)") (class "Default")
      (node (ref "H2") (pin "42") (pinfunction "42_42") (pintype "passive"))
      (node (ref "rxPI1") (pin "142") (pinfunction "CAM0_C_P_142") (pintype "passive"))
    )
    (net (code "147") (name "Net-(rxPI1B-CAM0_D0_N)") (class "Default")
      (node (ref "H2") (pin "28") (pinfunction "28_28") (pintype "passive"))
      (node (ref "rxPI1") (pin "128") (pinfunction "CAM0_D0_N_128") (pintype "passive"))
    )
    (net (code "148") (name "Net-(rxPI1B-CAM0_D0_P)") (class "Default")
      (node (ref "H2") (pin "30") (pinfunction "30_30") (pintype "passive"))
      (node (ref "rxPI1") (pin "130") (pinfunction "CAM0_D0_P_130") (pintype "passive"))
    )
    (net (code "149") (name "Net-(rxPI1B-CAM0_D1_N)") (class "Default")
      (node (ref "H2") (pin "34") (pinfunction "34_34") (pintype "passive"))
      (node (ref "rxPI1") (pin "134") (pinfunction "CAM0_D1_N_134") (pintype "passive"))
    )
    (net (code "150") (name "Net-(rxPI1B-CAM0_D1_P)") (class "Default")
      (node (ref "H2") (pin "36") (pinfunction "36_36") (pintype "passive"))
      (node (ref "rxPI1") (pin "136") (pinfunction "CAM0_D1_P_136") (pintype "passive"))
    )
    (net (code "151") (name "Net-(rxPI1B-CAM1_C_N)") (class "Default")
      (node (ref "H2") (pin "27") (pinfunction "27_27") (pintype "passive"))
      (node (ref "rxPI1") (pin "127") (pinfunction "CAM1_C_N_127") (pintype "passive"))
    )
    (net (code "152") (name "Net-(rxPI1B-CAM1_C_P)") (class "Default")
      (node (ref "H2") (pin "29") (pinfunction "29_29") (pintype "passive"))
      (node (ref "rxPI1") (pin "129") (pinfunction "CAM1_C_P_129") (pintype "passive"))
    )
    (net (code "153") (name "Net-(rxPI1B-CAM1_D0_N)") (class "Default")
      (node (ref "H2") (pin "15") (pinfunction "15_15") (pintype "passive"))
      (node (ref "rxPI1") (pin "115") (pinfunction "CAM1_D0_N_115") (pintype "passive"))
    )
    (net (code "154") (name "Net-(rxPI1B-CAM1_D0_P)") (class "Default")
      (node (ref "H2") (pin "17") (pinfunction "17_17") (pintype "passive"))
      (node (ref "rxPI1") (pin "117") (pinfunction "CAM1_D0_P_117") (pintype "passive"))
    )
    (net (code "155") (name "Net-(rxPI1B-CAM1_D1_N)") (class "Default")
      (node (ref "H2") (pin "21") (pinfunction "21_21") (pintype "passive"))
      (node (ref "rxPI1") (pin "121") (pinfunction "CAM1_D1_N_121") (pintype "passive"))
    )
    (net (code "156") (name "Net-(rxPI1B-CAM1_D1_P)") (class "Default")
      (node (ref "H2") (pin "23") (pinfunction "23_23") (pintype "passive"))
      (node (ref "rxPI1") (pin "123") (pinfunction "CAM1_D1_P_123") (pintype "passive"))
    )
    (net (code "157") (name "Net-(rxPI1B-CAM1_D2_N)") (class "Default")
      (node (ref "H2") (pin "33") (pinfunction "33_33") (pintype "passive"))
      (node (ref "rxPI1") (pin "133") (pinfunction "CAM1_D2_N_133") (pintype "passive"))
    )
    (net (code "158") (name "Net-(rxPI1B-CAM1_D2_P)") (class "Default")
      (node (ref "H2") (pin "35") (pinfunction "35_35") (pintype "passive"))
      (node (ref "rxPI1") (pin "135") (pinfunction "CAM1_D2_P_135") (pintype "passive"))
    )
    (net (code "159") (name "Net-(rxPI1B-CAM1_D3_N)") (class "Default")
      (node (ref "H2") (pin "39") (pinfunction "39_39") (pintype "passive"))
      (node (ref "rxPI1") (pin "139") (pinfunction "CAM1_D3_N_139") (pintype "passive"))
    )
    (net (code "160") (name "Net-(rxPI1B-CAM1_D3_P)") (class "Default")
      (node (ref "H2") (pin "41") (pinfunction "41_41") (pintype "passive"))
      (node (ref "rxPI1") (pin "141") (pinfunction "CAM1_D3_P_141") (pintype "passive"))
    )
    (net (code "161") (name "Net-(rxPI1B-DSI0_C_N)") (class "Default")
      (node (ref "H2") (pin "69") (pinfunction "69_69") (pintype "passive"))
      (node (ref "rxPI1") (pin "169") (pinfunction "DSI0_C_N_169") (pintype "passive"))
    )
    (net (code "162") (name "Net-(rxPI1B-DSI0_C_P)") (class "Default")
      (node (ref "H2") (pin "71") (pinfunction "71_71") (pintype "passive"))
      (node (ref "rxPI1") (pin "171") (pinfunction "DSI0_C_P_171") (pintype "passive"))
    )
    (net (code "163") (name "Net-(rxPI1B-DSI0_D0_N)") (class "Default")
      (node (ref "H2") (pin "57") (pinfunction "57_57") (pintype "passive"))
      (node (ref "rxPI1") (pin "157") (pinfunction "DSI0_D0_N_157") (pintype "passive"))
    )
    (net (code "164") (name "Net-(rxPI1B-DSI0_D0_P)") (class "Default")
      (node (ref "H2") (pin "59") (pinfunction "59_59") (pintype "passive"))
      (node (ref "rxPI1") (pin "159") (pinfunction "DSI0_D0_P_159") (pintype "passive"))
    )
    (net (code "165") (name "Net-(rxPI1B-DSI0_D1_N)") (class "Default")
      (node (ref "H2") (pin "63") (pinfunction "63_63") (pintype "passive"))
      (node (ref "rxPI1") (pin "163") (pinfunction "DSI0_D1_N_163") (pintype "passive"))
    )
    (net (code "166") (name "Net-(rxPI1B-DSI0_D1_P)") (class "Default")
      (node (ref "H2") (pin "65") (pinfunction "65_65") (pintype "passive"))
      (node (ref "rxPI1") (pin "165") (pinfunction "DSI0_D1_P_165") (pintype "passive"))
    )
    (net (code "167") (name "Net-(rxPI1B-DSI1_C_N)") (class "Default")
      (node (ref "H2") (pin "87") (pinfunction "87_87") (pintype "passive"))
      (node (ref "rxPI1") (pin "187") (pinfunction "DSI1_C_N_187") (pintype "passive"))
    )
    (net (code "168") (name "Net-(rxPI1B-DSI1_C_P)") (class "Default")
      (node (ref "H2") (pin "89") (pinfunction "89_89") (pintype "passive"))
      (node (ref "rxPI1") (pin "189") (pinfunction "DSI1_C_P_189") (pintype "passive"))
    )
    (net (code "169") (name "Net-(rxPI1B-DSI1_D0_N)") (class "Default")
      (node (ref "H2") (pin "75") (pinfunction "75_75") (pintype "passive"))
      (node (ref "rxPI1") (pin "175") (pinfunction "DSI1_D0_N_175") (pintype "passive"))
    )
    (net (code "170") (name "Net-(rxPI1B-DSI1_D0_P)") (class "Default")
      (node (ref "H2") (pin "77") (pinfunction "77_77") (pintype "passive"))
      (node (ref "rxPI1") (pin "177") (pinfunction "DSI1_D0_P_177") (pintype "passive"))
    )
    (net (code "171") (name "Net-(rxPI1B-DSI1_D1_N)") (class "Default")
      (node (ref "H2") (pin "81") (pinfunction "81_81") (pintype "passive"))
      (node (ref "rxPI1") (pin "181") (pinfunction "DSI1_D1_N_181") (pintype "passive"))
    )
    (net (code "172") (name "Net-(rxPI1B-DSI1_D1_P)") (class "Default")
      (node (ref "H2") (pin "83") (pinfunction "83_83") (pintype "passive"))
      (node (ref "rxPI1") (pin "183") (pinfunction "DSI1_D1_P_183") (pintype "passive"))
    )
    (net (code "173") (name "Net-(rxPI1B-DSI1_D2_N)") (class "Default")
      (node (ref "H2") (pin "93") (pinfunction "93_93") (pintype "passive"))
      (node (ref "rxPI1") (pin "193") (pinfunction "DSI1_D2_N_193") (pintype "passive"))
    )
    (net (code "174") (name "Net-(rxPI1B-DSI1_D2_P)") (class "Default")
      (node (ref "H2") (pin "95") (pinfunction "95_95") (pintype "passive"))
      (node (ref "rxPI1") (pin "195") (pinfunction "DSI1_D2_P_195") (pintype "passive"))
    )
    (net (code "175") (name "Net-(rxPI1B-DSI1_D3_N)") (class "Default")
      (node (ref "H2") (pin "94") (pinfunction "94_94") (pintype "passive"))
      (node (ref "rxPI1") (pin "194") (pinfunction "DSI1_D3_N_194") (pintype "passive"))
    )
    (net (code "176") (name "Net-(rxPI1B-DSI1_D3_P)") (class "Default")
      (node (ref "H2") (pin "96") (pinfunction "96_96") (pintype "passive"))
      (node (ref "rxPI1") (pin "196") (pinfunction "DSI1_D3_P_196") (pintype "passive"))
    )
    (net (code "177") (name "Net-(rxPI1B-VDAC_COMP)") (class "Default")
      (node (ref "H2") (pin "11") (pinfunction "11_11") (pintype "passive"))
      (node (ref "rxPI1") (pin "111") (pinfunction "VDAC_COMP_111") (pintype "passive"))
    )
    (net (code "178") (name "Net-(rxPI1C-BT_HOST_WAKE)") (class "Default")
      (node (ref "J3") (pin "86") (pinfunction "86_86") (pintype "passive"))
      (node (ref "rxPI1") (pin "285") (pinfunction "BT_HOST_WAKE_285") (pintype "passive"))
    )
    (net (code "179") (name "Net-(rxPI1C-BT_REG_ON_H)") (class "Default")
      (node (ref "J3") (pin "97") (pinfunction "97_97") (pintype "passive"))
      (node (ref "rxPI1") (pin "298") (pinfunction "BT_REG_ON_H_298") (pintype "passive"))
    )
    (net (code "180") (name "Net-(rxPI1C-GPIO0_C2)") (class "Default")
      (node (ref "J3") (pin "94") (pinfunction "94_94") (pintype "passive"))
      (node (ref "rxPI1") (pin "293") (pinfunction "GPIO0_C2_293") (pintype "passive"))
    )
    (net (code "181") (name "Net-(rxPI1C-GPIO0_D3)") (class "Default")
      (node (ref "J3") (pin "93") (pinfunction "93_93") (pintype "passive"))
      (node (ref "rxPI1") (pin "294") (pinfunction "GPIO0_D3_294") (pintype "passive"))
    )
    (net (code "182") (name "Net-(rxPI1C-GPIO1_B6_CAM2_CLK)") (class "Default")
      (node (ref "J3") (pin "9") (pinfunction "9_9") (pintype "passive"))
      (node (ref "rxPI1") (pin "210") (pinfunction "GPIO1_B6_CAM2_CLK_210") (pintype "passive"))
    )
    (net (code "183") (name "Net-(rxPI1C-GPIO1_B7)") (class "Default")
      (node (ref "J3") (pin "11") (pinfunction "11_11") (pintype "passive"))
      (node (ref "rxPI1") (pin "212") (pinfunction "GPIO1_B7_212") (pintype "passive"))
    )
    (net (code "184") (name "Net-(rxPI1C-GPIO1_C1)") (class "Default")
      (node (ref "J3") (pin "19") (pinfunction "19_19") (pintype "passive"))
      (node (ref "rxPI1") (pin "220") (pinfunction "GPIO1_C1_220") (pintype "passive"))
    )
    (net (code "185") (name "Net-(rxPI1C-GPIO1_C4_S)") (class "Default")
      (node (ref "J3") (pin "80") (pinfunction "80_80") (pintype "passive"))
      (node (ref "rxPI1") (pin "279") (pinfunction "GPIO1_C4_S_279") (pintype "passive"))
    )
    (net (code "186") (name "Net-(rxPI1C-GPIO1_C6_S)") (class "Default")
      (node (ref "J3") (pin "76") (pinfunction "76_76") (pintype "passive"))
      (node (ref "rxPI1") (pin "275") (pinfunction "GPIO1_C6_S_275") (pintype "passive"))
    )
    (net (code "187") (name "Net-(rxPI1C-GPIO1_D0)") (class "Default")
      (node (ref "J3") (pin "43") (pinfunction "43_43") (pintype "passive"))
      (node (ref "rxPI1") (pin "244") (pinfunction "GPIO1_D0_244") (pintype "passive"))
    )
    (net (code "188") (name "Net-(rxPI1C-GPIO1_D1)") (class "Default")
      (node (ref "J3") (pin "45") (pinfunction "45_45") (pintype "passive"))
      (node (ref "rxPI1") (pin "246") (pinfunction "GPIO1_D1_246") (pintype "passive"))
    )
    (net (code "189") (name "Net-(rxPI1C-GPIO1_D2)") (class "Default")
      (node (ref "J3") (pin "84") (pinfunction "84_84") (pintype "passive"))
      (node (ref "rxPI1") (pin "283") (pinfunction "GPIO1_D2_283") (pintype "passive"))
    )
    (net (code "190") (name "Net-(rxPI1C-GPIO1_D5_S)") (class "Default")
      (node (ref "J3") (pin "78") (pinfunction "78_78") (pintype "passive"))
      (node (ref "rxPI1") (pin "277") (pinfunction "GPIO1_D5_S_277") (pintype "passive"))
    )
    (net (code "191") (name "Net-(rxPI1C-GPIO3_B7)") (class "Default")
      (node (ref "J3") (pin "5") (pinfunction "5_5") (pintype "passive"))
      (node (ref "rxPI1") (pin "206") (pinfunction "GPIO3_B7_206") (pintype "passive"))
    )
    (net (code "192") (name "Net-(rxPI1C-GPIO3_C0)") (class "Default")
      (node (ref "J3") (pin "3") (pinfunction "3_3") (pintype "passive"))
      (node (ref "rxPI1") (pin "204") (pinfunction "GPIO3_C0_204") (pintype "passive"))
    )
    (net (code "193") (name "Net-(rxPI1C-GPIO4_A4)") (class "Default")
      (node (ref "J3") (pin "37") (pinfunction "37_37") (pintype "passive"))
      (node (ref "rxPI1") (pin "238") (pinfunction "GPIO4_A4_238") (pintype "passive"))
    )
    (net (code "194") (name "Net-(rxPI1C-GPIO4_A5)") (class "Default")
      (node (ref "J3") (pin "39") (pinfunction "39_39") (pintype "passive"))
      (node (ref "rxPI1") (pin "240") (pinfunction "GPIO4_A5_240") (pintype "passive"))
    )
    (net (code "195") (name "Net-(rxPI1C-GPIO4_A6)") (class "Default")
      (node (ref "J3") (pin "90") (pinfunction "90_90") (pintype "passive"))
      (node (ref "rxPI1") (pin "289") (pinfunction "GPIO4_A6_289") (pintype "passive"))
    )
    (net (code "196") (name "Net-(rxPI1C-GPIO4_A7)") (class "Default")
      (node (ref "J3") (pin "88") (pinfunction "88_88") (pintype "passive"))
      (node (ref "rxPI1") (pin "287") (pinfunction "GPIO4_A7_287") (pintype "passive"))
    )
    (net (code "197") (name "Net-(rxPI1C-HP_DET_L)") (class "Default")
      (node (ref "J3") (pin "35") (pinfunction "35_35") (pintype "passive"))
      (node (ref "rxPI1") (pin "236") (pinfunction "HP_DET_L_236") (pintype "passive"))
    )
    (net (code "198") (name "Net-(rxPI1C-LCD_PWREN_H)") (class "Default")
      (node (ref "J3") (pin "33") (pinfunction "33_33") (pintype "passive"))
      (node (ref "rxPI1") (pin "234") (pinfunction "LCD_PWREN_H_234") (pintype "passive"))
    )
    (net (code "199") (name "Net-(rxPI1C-PCIE20_2_REFCLKN)") (class "Default")
      (node (ref "J3") (pin "42") (pinfunction "42_42") (pintype "passive"))
      (node (ref "rxPI1") (pin "241") (pinfunction "PCIE20_2_REFCLKN_241") (pintype "passive"))
    )
    (net (code "200") (name "Net-(rxPI1C-PCIE20_2_REFCLKP)") (class "Default")
      (node (ref "J3") (pin "40") (pinfunction "40_40") (pintype "passive"))
      (node (ref "rxPI1") (pin "239") (pinfunction "PCIE20_2_REFCLKP_239") (pintype "passive"))
    )
    (net (code "201") (name "Net-(rxPI1C-PWM11_M3)") (class "Default")
      (node (ref "J3") (pin "17") (pinfunction "17_17") (pintype "passive"))
      (node (ref "rxPI1") (pin "218") (pinfunction "PWM11_M3_218") (pintype "passive"))
    )
    (net (code "202") (name "Net-(rxPI1C-RTC_INT_L)") (class "Default")
      (node (ref "J3") (pin "82") (pinfunction "82_82") (pintype "passive"))
      (node (ref "rxPI1") (pin "281") (pinfunction "RTC_INT_L_281") (pintype "passive"))
    )
    (net (code "203") (name "Net-(rxPI1C-SARADC_VIN0_KEY{slash}RECOVERY)") (class "Default")
      (node (ref "J3") (pin "25") (pinfunction "25_25") (pintype "passive"))
      (node (ref "rxPI1") (pin "226") (pinfunction "SARADC_VIN0_KEY/RECOVERY_226") (pintype "passive"))
    )
    (net (code "204") (name "Net-(rxPI1C-SARADC_VIN1_DC)") (class "Default")
      (node (ref "J3") (pin "27") (pinfunction "27_27") (pintype "passive"))
      (node (ref "rxPI1") (pin "228") (pinfunction "SARADC_VIN1_DC_228") (pintype "passive"))
    )
    (net (code "205") (name "Net-(rxPI1C-SARADC_VIN2_HP_HOOK)") (class "Default")
      (node (ref "J3") (pin "29") (pinfunction "29_29") (pintype "passive"))
      (node (ref "rxPI1") (pin "230") (pinfunction "SARADC_VIN2_HP_HOOK_230") (pintype "passive"))
    )
    (net (code "206") (name "Net-(rxPI1C-SDMMC_DET_L)") (class "Default")
      (node (ref "J3") (pin "73") (pinfunction "73_73") (pintype "passive"))
      (node (ref "rxPI1") (pin "274") (pinfunction "SDMMC_DET_L_274") (pintype "passive"))
    )
    (net (code "207") (name "Net-(rxPI1C-TYPEC0_OTG_VBUSDET)") (class "Default")
      (node (ref "J3") (pin "98") (pinfunction "98_98") (pintype "passive"))
      (node (ref "rxPI1") (pin "297") (pinfunction "TYPEC0_OTG_VBUSDET_297") (pintype "passive"))
    )
    (net (code "208") (name "Net-(rxPI1C-TYPEC0_SBU1)") (class "Default")
      (node (ref "J3") (pin "4") (pinfunction "4_4") (pintype "passive"))
      (node (ref "rxPI1") (pin "203") (pinfunction "TYPEC0_SBU1_203") (pintype "passive"))
    )
    (net (code "209") (name "Net-(rxPI1C-TYPEC0_SBU1_DC)") (class "Default")
      (node (ref "J3") (pin "7") (pinfunction "7_7") (pintype "passive"))
      (node (ref "rxPI1") (pin "208") (pinfunction "TYPEC0_SBU1_DC_208") (pintype "passive"))
    )
    (net (code "210") (name "Net-(rxPI1C-TYPEC0_SBU2)") (class "Default")
      (node (ref "J3") (pin "6") (pinfunction "6_6") (pintype "passive"))
      (node (ref "rxPI1") (pin "205") (pinfunction "TYPEC0_SBU2_205") (pintype "passive"))
    )
    (net (code "211") (name "Net-(rxPI1C-TYPEC0_SBU2_DC)") (class "Default")
      (node (ref "J3") (pin "13") (pinfunction "13_13") (pintype "passive"))
      (node (ref "rxPI1") (pin "214") (pinfunction "TYPEC0_SBU2_DC_214") (pintype "passive"))
    )
    (net (code "212") (name "Net-(rxPI1C-TYPEC0_SSRX2N)") (class "Default")
      (node (ref "J3") (pin "24") (pinfunction "24_24") (pintype "passive"))
      (node (ref "rxPI1") (pin "223") (pinfunction "TYPEC0_SSRX2N_223") (pintype "passive"))
    )
    (net (code "213") (name "Net-(rxPI1C-TYPEC0_SSRX2P)") (class "Default")
      (node (ref "J3") (pin "22") (pinfunction "22_22") (pintype "passive"))
      (node (ref "rxPI1") (pin "221") (pinfunction "TYPEC0_SSRX2P_221") (pintype "passive"))
    )
    (net (code "214") (name "Net-(rxPI1C-TYPEC0_SSTX2N)") (class "Default")
      (node (ref "J3") (pin "30") (pinfunction "30_30") (pintype "passive"))
      (node (ref "rxPI1") (pin "229") (pinfunction "TYPEC0_SSTX2N_229") (pintype "passive"))
    )
    (net (code "215") (name "Net-(rxPI1C-TYPEC0_SSTX2P)") (class "Default")
      (node (ref "J3") (pin "28") (pinfunction "28_28") (pintype "passive"))
      (node (ref "rxPI1") (pin "227") (pinfunction "TYPEC0_SSTX2P_227") (pintype "passive"))
    )
    (net (code "216") (name "Net-(rxPI1C-TYPEC5V_PWREN_H)") (class "Default")
      (node (ref "J3") (pin "96") (pinfunction "96_96") (pintype "passive"))
      (node (ref "rxPI1") (pin "295") (pinfunction "TYPEC5V_PWREN_H_295") (pintype "passive"))
    )
    (net (code "217") (name "Net-(rxPI1C-VCC_SD_3V3_S3)") (class "Default")
      (node (ref "J3") (pin "91") (pinfunction "91_91") (pintype "passive"))
      (node (ref "R3") (pin "2") (pinfunction "2_2") (pintype "passive"))
      (node (ref "rxPI1") (pin "292") (pinfunction "VCC_SD_3V3_S3_292") (pintype "passive"))
    )
    (net (code "218") (name "Net-(rxPI1C-WIFI_PWR_EN)") (class "Default")
      (node (ref "J3") (pin "23") (pinfunction "23_23") (pintype "passive"))
      (node (ref "rxPI1") (pin "224") (pinfunction "WIFI_PWR_EN_224") (pintype "passive"))
    )
    (net (code "219") (name "PCIe_CLK_N") (class "Default")
      (node (ref "H2") (pin "12") (pinfunction "12_12") (pintype "passive"))
      (node (ref "HB") (pin "11") (pinfunction "11_11") (pintype "passive"))
      (node (ref "rPI1") (pin "112") (pinfunction "PCIe_CLK_N_112") (pintype "passive"))
      (node (ref "rxPI1") (pin "112") (pinfunction "PCIe_CLK_N_112") (pintype "passive"))
    )
    (net (code "220") (name "PCIe_CLK_P") (class "Default")
      (node (ref "H2") (pin "10") (pinfunction "10_10") (pintype "passive"))
      (node (ref "HB") (pin "9") (pinfunction "9_9") (pintype "passive"))
      (node (ref "rPI1") (pin "110") (pinfunction "PCIe_CLK_P_110") (pintype "passive"))
      (node (ref "rxPI1") (pin "110") (pinfunction "PCIe_CLK_P_110") (pintype "passive"))
    )
    (net (code "221") (name "PCIe_CLK_nREQ") (class "Default")
      (node (ref "H2") (pin "2") (pinfunction "2_2") (pintype "passive"))
      (node (ref "HB") (pin "1") (pinfunction "1_1") (pintype "passive"))
      (node (ref "rPI1") (pin "102") (pinfunction "PCIe_CLK_nREQ_102") (pintype "passive"))
      (node (ref "rxPI1") (pin "102") (pinfunction "PCIe_CLK_nREQ_102") (pintype "passive"))
    )
    (net (code "222") (name "PCIe_RX_N") (class "Default")
      (node (ref "H2") (pin "18") (pinfunction "18_18") (pintype "passive"))
      (node (ref "HB") (pin "17") (pinfunction "17_17") (pintype "passive"))
      (node (ref "rPI1") (pin "118") (pinfunction "PCIe_RX_N_118") (pintype "passive"))
      (node (ref "rxPI1") (pin "118") (pinfunction "PCIe_RX_N_118") (pintype "passive"))
    )
    (net (code "223") (name "PCIe_RX_P") (class "Default")
      (node (ref "H2") (pin "16") (pinfunction "16_16") (pintype "passive"))
      (node (ref "HB") (pin "15") (pinfunction "15_15") (pintype "passive"))
      (node (ref "rPI1") (pin "116") (pinfunction "PCIe_RX_P_116") (pintype "passive"))
      (node (ref "rxPI1") (pin "116") (pinfunction "PCIe_RX_P_116") (pintype "passive"))
    )
    (net (code "224") (name "PCIe_TX_N") (class "Default")
      (node (ref "H2") (pin "24") (pinfunction "24_24") (pintype "passive"))
      (node (ref "HB") (pin "23") (pinfunction "23_23") (pintype "passive"))
      (node (ref "rPI1") (pin "124") (pinfunction "PCIe_TX_N_124") (pintype "passive"))
      (node (ref "rxPI1") (pin "124") (pinfunction "PCIe_TX_N_124") (pintype "passive"))
    )
    (net (code "225") (name "PCIe_TX_P") (class "Default")
      (node (ref "H2") (pin "22") (pinfunction "22_22") (pintype "passive"))
      (node (ref "HB") (pin "21") (pinfunction "21_21") (pintype "passive"))
      (node (ref "rPI1") (pin "122") (pinfunction "PCIe_TX_P_122") (pintype "passive"))
      (node (ref "rxPI1") (pin "122") (pinfunction "PCIe_TX_P_122") (pintype "passive"))
    )
    (net (code "226") (name "PCIe_nRST") (class "Default")
      (node (ref "H2") (pin "9") (pinfunction "9_9") (pintype "passive"))
      (node (ref "HB") (pin "10") (pinfunction "10_10") (pintype "passive"))
      (node (ref "rPI1") (pin "109") (pinfunction "PCIe_nRST_109") (pintype "passive"))
      (node (ref "rxPI1") (pin "109") (pinfunction "PCIe_nRST_109") (pintype "passive"))
    )
    (net (code "227") (name "PRG_CC1") (class "Default")
      (node (ref "J1") (pin "A5") (pinfunction "CC1_A5") (pintype "bidirectional"))
      (node (ref "R1") (pin "1") (pinfunction "1_1") (pintype "passive"))
      (node (ref "U1") (pin "10") (pinfunction "CC1_10") (pintype "bidirectional"))
      (node (ref "U1") (pin "11") (pinfunction "CC1_11") (pintype "bidirectional"))
    )
    (net (code "228") (name "PRG_CC2") (class "Default")
      (node (ref "J1") (pin "B5") (pinfunction "CC2_B5") (pintype "bidirectional"))
      (node (ref "U1") (pin "1") (pinfunction "CC2_1") (pintype "bidirectional"))
      (node (ref "U1") (pin "14") (pinfunction "CC2_14") (pintype "bidirectional"))
    )
    (net (code "229") (name "RD_CC1") (class "Default")
      (node (ref "HB") (pin "98") (pinfunction "98_98") (pintype "passive"))
      (node (ref "R1") (pin "2") (pinfunction "2_2") (pintype "passive"))
      (node (ref "rPI1") (pin "197") (pinfunction "GND_197") (pintype "passive"))
    )
    (net (code "230") (name "Res104") (class "Default")
      (node (ref "H2") (pin "4") (pinfunction "4_4") (pintype "passive"))
      (node (ref "HB") (pin "3") (pinfunction "3_3") (pintype "passive"))
      (node (ref "rPI1") (pin "104") (pinfunction "PCIE_nWAKE_104") (pintype "passive"))
      (node (ref "rxPI1") (pin "104") (pinfunction "Reserved_104") (pintype "passive"))
    )
    (net (code "231") (name "Res106") (class "Default")
      (node (ref "H2") (pin "6") (pinfunction "6_6") (pintype "passive"))
      (node (ref "HB") (pin "5") (pinfunction "5_5") (pintype "passive"))
      (node (ref "rPI1") (pin "106") (pinfunction "PCIE_PWR_EN_106") (pintype "passive"))
      (node (ref "rxPI1") (pin "106") (pinfunction "Reserved_106") (pintype "passive"))
    )
    (net (code "232") (name "USB2_N") (class "Default")
      (node (ref "HB") (pin "4") (pinfunction "4_4") (pintype "passive"))
      (node (ref "J3") (pin "64") (pinfunction "64_64") (pintype "passive"))
      (node (ref "rPI1") (pin "103") (pinfunction "USB2_N_103") (pintype "passive"))
      (node (ref "rxPI1") (pin "263") (pinfunction "USB20_HOST0_DP_263") (pintype "passive"))
    )
    (net (code "233") (name "USB2_P") (class "Default")
      (node (ref "HB") (pin "6") (pinfunction "6_6") (pintype "passive"))
      (node (ref "J3") (pin "66") (pinfunction "66_66") (pintype "passive"))
      (node (ref "rPI1") (pin "105") (pinfunction "USB2_P_105") (pintype "passive"))
      (node (ref "rxPI1") (pin "265") (pinfunction "USB20_HOST0_DM_265") (pintype "passive"))
    )
    (net (code "234") (name "USB30_RX1_N") (class "Default")
      (node (ref "HB") (pin "27") (pinfunction "27_27") (pintype "passive"))
      (node (ref "J3") (pin "12") (pinfunction "12_12") (pintype "passive"))
      (node (ref "rPI1") (pin "128") (pinfunction "USB3-0-RX_N_128") (pintype "passive"))
      (node (ref "rxPI1") (pin "211") (pinfunction "TYPEC0_SSRX1N_211") (pintype "passive"))
    )
    (net (code "235") (name "USB30_RX1_P") (class "Default")
      (node (ref "HB") (pin "29") (pinfunction "29_29") (pintype "passive"))
      (node (ref "J3") (pin "10") (pinfunction "10_10") (pintype "passive"))
      (node (ref "rPI1") (pin "130") (pinfunction "USB3-0-RX_P_130") (pintype "passive"))
      (node (ref "rxPI1") (pin "209") (pinfunction "TYPEC0_SSRX1P_209") (pintype "passive"))
    )
    (net (code "236") (name "USB30_TX1_N") (class "Default")
      (node (ref "HB") (pin "39") (pinfunction "39_39") (pintype "passive"))
      (node (ref "J3") (pin "18") (pinfunction "18_18") (pintype "passive"))
      (node (ref "rPI1") (pin "140") (pinfunction "USB3-0-TX_N_140") (pintype "passive"))
      (node (ref "rxPI1") (pin "217") (pinfunction "TYPEC0_SSTX1N_217") (pintype "passive"))
    )
    (net (code "237") (name "USB30_TX1_P") (class "Default")
      (node (ref "HB") (pin "41") (pinfunction "41_41") (pintype "passive"))
      (node (ref "J3") (pin "16") (pinfunction "16_16") (pintype "passive"))
      (node (ref "rPI1") (pin "142") (pinfunction "USB3-0-TX_P_142") (pintype "passive"))
      (node (ref "rxPI1") (pin "215") (pinfunction "TYPEC0_SSTX1P_215") (pintype "passive"))
    )
    (net (code "238") (name "USB31_D_N") (class "Default")
      (node (ref "HB") (pin "66") (pinfunction "66_66") (pintype "passive"))
      (node (ref "J3") (pin "48") (pinfunction "48_48") (pintype "passive"))
      (node (ref "rPI1") (pin "165") (pinfunction "USB3-1-D_N_165") (pintype "passive"))
      (node (ref "rxPI1") (pin "247") (pinfunction "USB20_HOST1_DM_247") (pintype "passive"))
    )
    (net (code "239") (name "USB31_D_P") (class "Default")
      (node (ref "HB") (pin "64") (pinfunction "64_64") (pintype "passive"))
      (node (ref "J3") (pin "46") (pinfunction "46_46") (pintype "passive"))
      (node (ref "rPI1") (pin "163") (pinfunction "USB3-1-D_P_163") (pintype "passive"))
      (node (ref "rxPI1") (pin "245") (pinfunction "USB20_HOST1_DP_245") (pintype "passive"))
    )
    (net (code "240") (name "USB31_RX_N") (class "Default")
      (node (ref "HB") (pin "58") (pinfunction "58_58") (pintype "passive"))
      (node (ref "J3") (pin "60") (pinfunction "60_60") (pintype "passive"))
      (node (ref "rPI1") (pin "157") (pinfunction "USB3-1-RX_N_157") (pintype "passive"))
      (node (ref "rxPI1") (pin "259") (pinfunction "C42_-_RXN_259") (pintype "passive"))
    )
    (net (code "241") (name "USB31_RX_P") (class "Default")
      (node (ref "HB") (pin "60") (pinfunction "60_60") (pintype "passive"))
      (node (ref "J3") (pin "58") (pinfunction "58_58") (pintype "passive"))
      (node (ref "rPI1") (pin "159") (pinfunction "USB3-1-RX_P_159") (pintype "passive"))
      (node (ref "rxPI1") (pin "257") (pinfunction "D42_-_RXP_257") (pintype "passive"))
    )
    (net (code "242") (name "USB31_TX_N") (class "Default")
      (node (ref "HB") (pin "70") (pinfunction "70_70") (pintype "passive"))
      (node (ref "J3") (pin "54") (pinfunction "54_54") (pintype "passive"))
      (node (ref "rPI1") (pin "169") (pinfunction "USB3-1-TX_N_169") (pintype "passive"))
      (node (ref "rxPI1") (pin "253") (pinfunction "D41_-_TXN_253") (pintype "passive"))
    )
    (net (code "243") (name "USB31_TX_P") (class "Default")
      (node (ref "HB") (pin "72") (pinfunction "72_72") (pintype "passive"))
      (node (ref "J3") (pin "52") (pinfunction "52_52") (pintype "passive"))
      (node (ref "rPI1") (pin "171") (pinfunction "USB3-1-TX_P_171") (pintype "passive"))
      (node (ref "rxPI1") (pin "251") (pinfunction "E41_-_TXP_251") (pintype "passive"))
    )
    (net (code "244") (name "USBP_D_N") (class "Default")
      (node (ref "D1") (pin "6") (pinfunction "I/O1_6") (pintype "bidirectional"))
      (node (ref "J1") (pin "A7") (pinfunction "DN1_A7") (pintype "bidirectional"))
      (node (ref "J1") (pin "B7") (pinfunction "DN2_B7") (pintype "bidirectional"))
    )
    (net (code "245") (name "USBP_D_P") (class "Default")
      (node (ref "D1") (pin "4") (pinfunction "I/O2_4") (pintype "bidirectional"))
      (node (ref "J1") (pin "A6") (pinfunction "DP1_A6") (pintype "bidirectional"))
      (node (ref "J1") (pin "B6") (pinfunction "DP2_B6") (pintype "bidirectional"))
    )
    (net (code "246") (name "USB_OTG_D_N") (class "Default")
      (node (ref "H2") (pin "3") (pinfunction "3_3") (pintype "passive"))
      (node (ref "HB") (pin "33") (pinfunction "33_33") (pintype "passive"))
      (node (ref "L1") (pin "1") (pinfunction "1_1") (pintype "passive"))
      (node (ref "rPI1") (pin "134") (pinfunction "USB3-0-D_P_134") (pintype "passive"))
      (node (ref "rxPI1") (pin "103") (pinfunction "USB2_N_103") (pintype "passive"))
    )
    (net (code "247") (name "USB_OTG_D_P") (class "Default")
      (node (ref "H2") (pin "5") (pinfunction "5_5") (pintype "passive"))
      (node (ref "HB") (pin "35") (pinfunction "35_35") (pintype "passive"))
      (node (ref "L1") (pin "2") (pinfunction "2_2") (pintype "passive"))
      (node (ref "rPI1") (pin "136") (pinfunction "USB3-0-D_N_136") (pintype "passive"))
      (node (ref "rxPI1") (pin "105") (pinfunction "USB2_P_105") (pintype "passive"))
    )
    (net (code "248") (name "USB_OTG_ID") (class "Default")
      (node (ref "H2") (pin "1") (pinfunction "1_1") (pintype "passive"))
      (node (ref "HB") (pin "2") (pinfunction "2_2") (pintype "passive"))
      (node (ref "rPI1") (pin "101") (pinfunction "USB_OTG_ID_101") (pintype "passive"))
      (node (ref "rxPI1") (pin "101") (pinfunction "USB_OTG_ID_101") (pintype "passive"))
    )
    (net (code "249") (name "VCC_3V3_S3") (class "Default")
      (node (ref "H1") (pin "84") (pinfunction "84_84") (pintype "passive"))
      (node (ref "HA") (pin "83") (pinfunction "83_83") (pintype "passive"))
      (node (ref "R2") (pin "2") (pinfunction "2_2") (pintype "passive"))
      (node (ref "R3") (pin "1") (pinfunction "1_1") (pintype "passive"))
      (node (ref "U1") (pin "3") (pinfunction "VDD_3") (pintype "power_in"))
      (node (ref "U1") (pin "4") (pinfunction "VDD_4") (pintype "power_in"))
      (node (ref "rPI1") (pin "84") (pinfunction "+3.3v_(Output)_84") (pintype "passive"))
      (node (ref "rxPI1") (pin "84") (pinfunction "+3.3v_(Output)_84") (pintype "passive"))
    )
    (net (code "250") (name "unconnected-(J1-SBU1-PadA8)") (class "Default")
      (node (ref "J1") (pin "A8") (pinfunction "SBU1_A8") (pintype "bidirectional"))
    )
    (net (code "251") (name "unconnected-(J1-SBU2-PadB8)") (class "Default")
      (node (ref "J1") (pin "B8") (pinfunction "SBU2_B8") (pintype "bidirectional"))
    )
  )
)
